# MSP-EXP430F5529LP.net
KiCad netlist of a schematic drawn in EAGLE
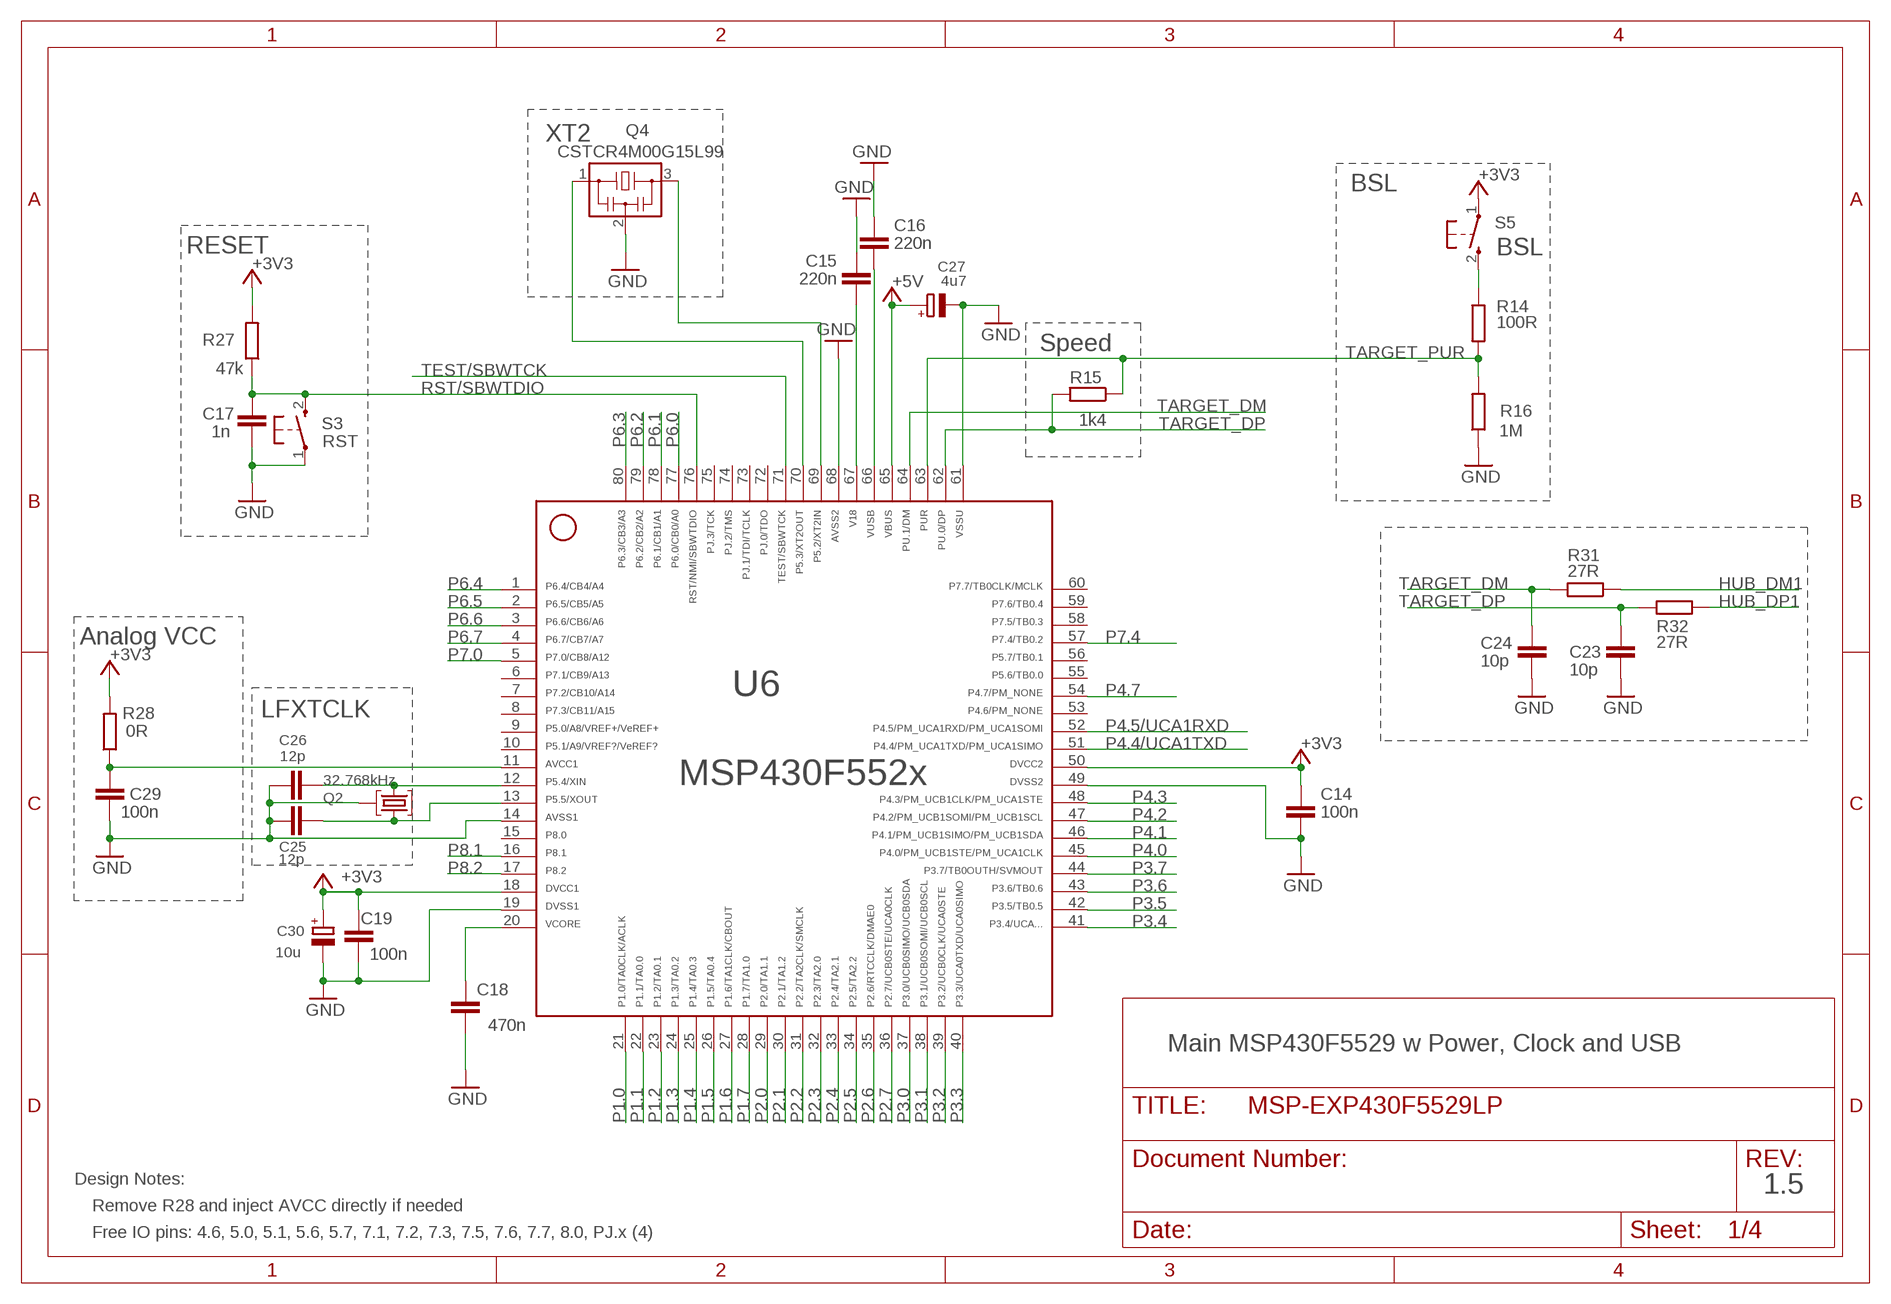
[diagram p0: schematic, sheet 1]
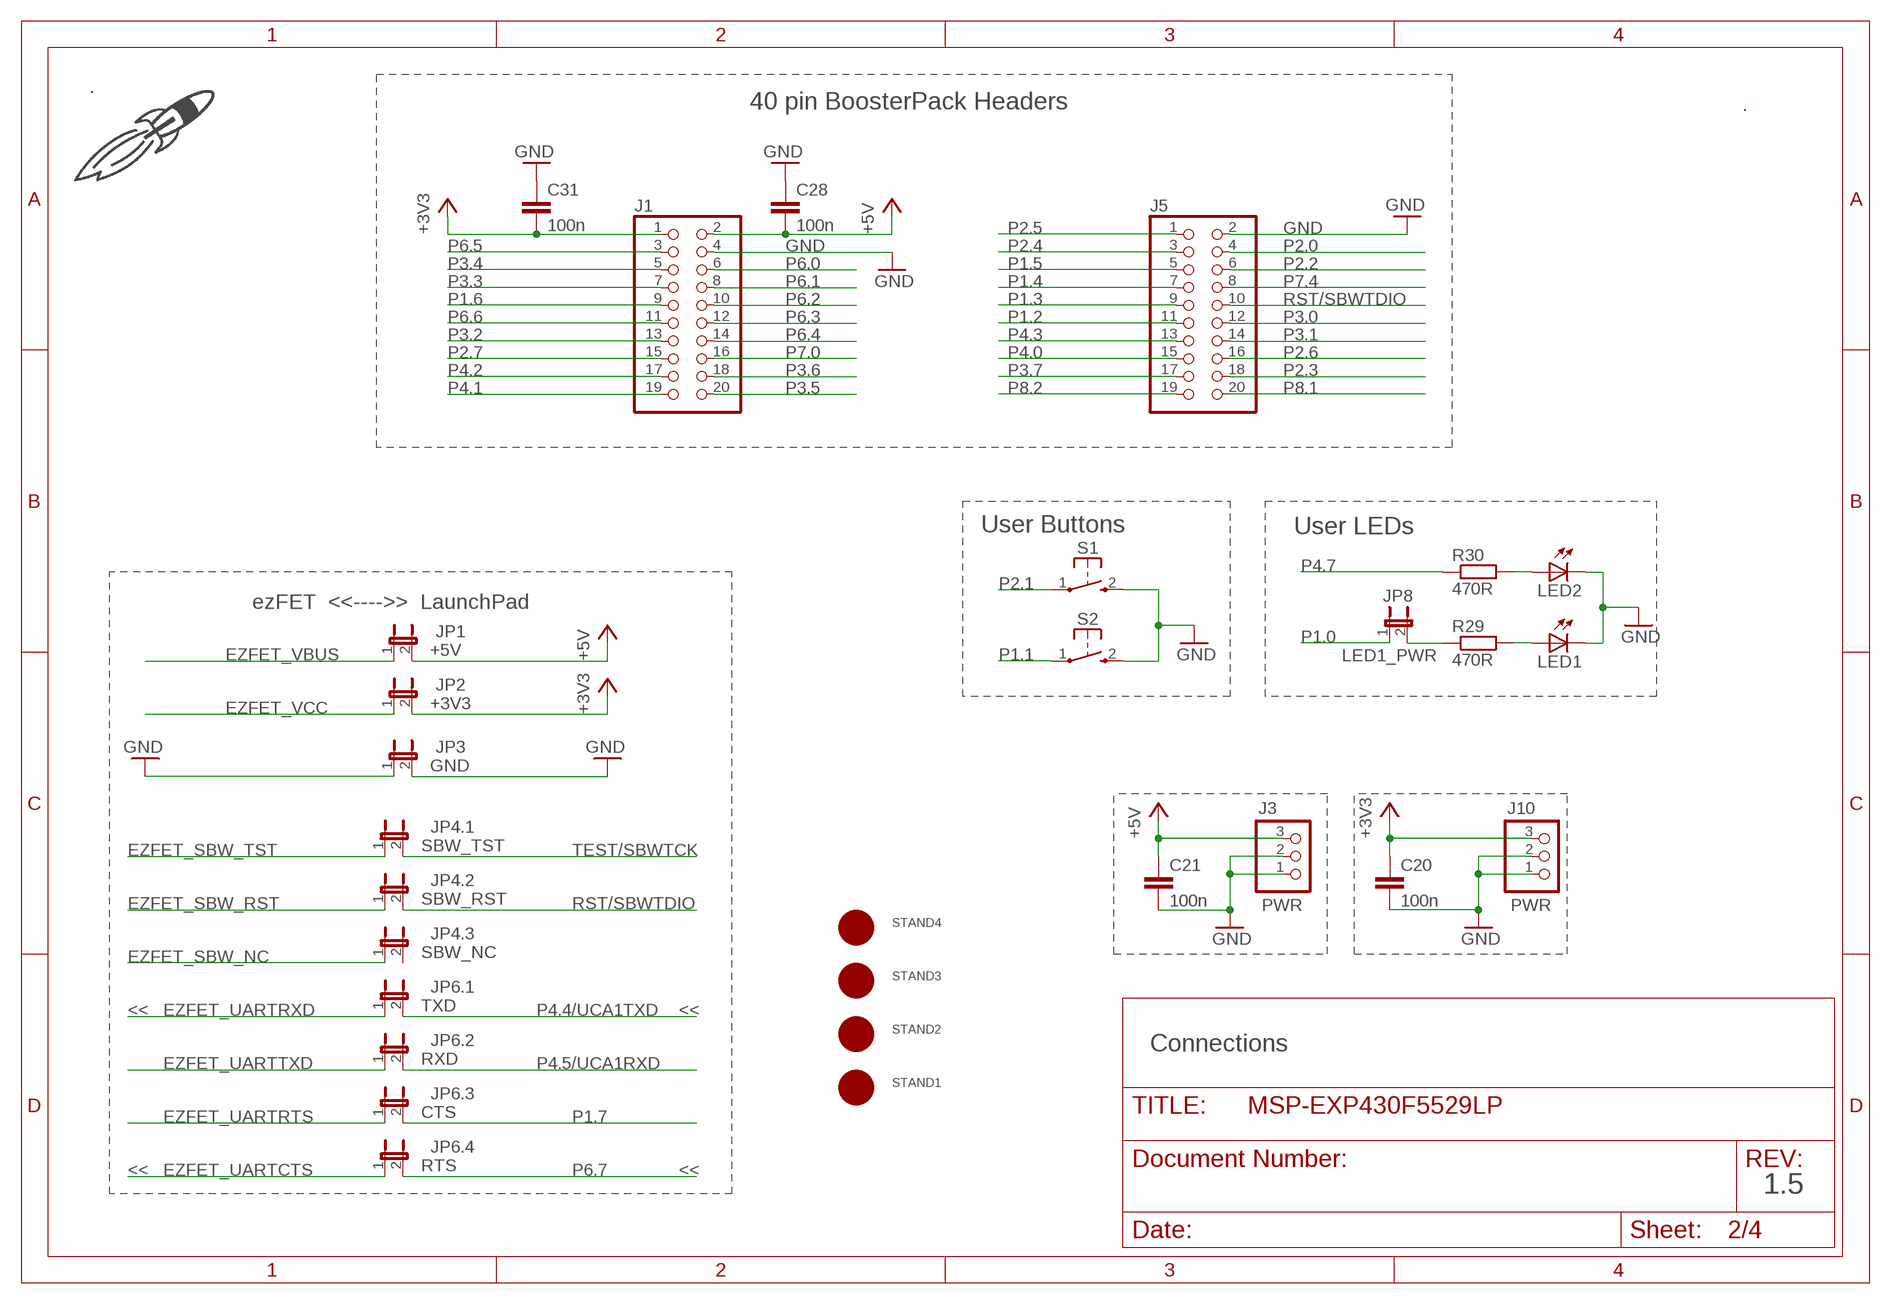
[diagram p1: schematic, sheet 2]
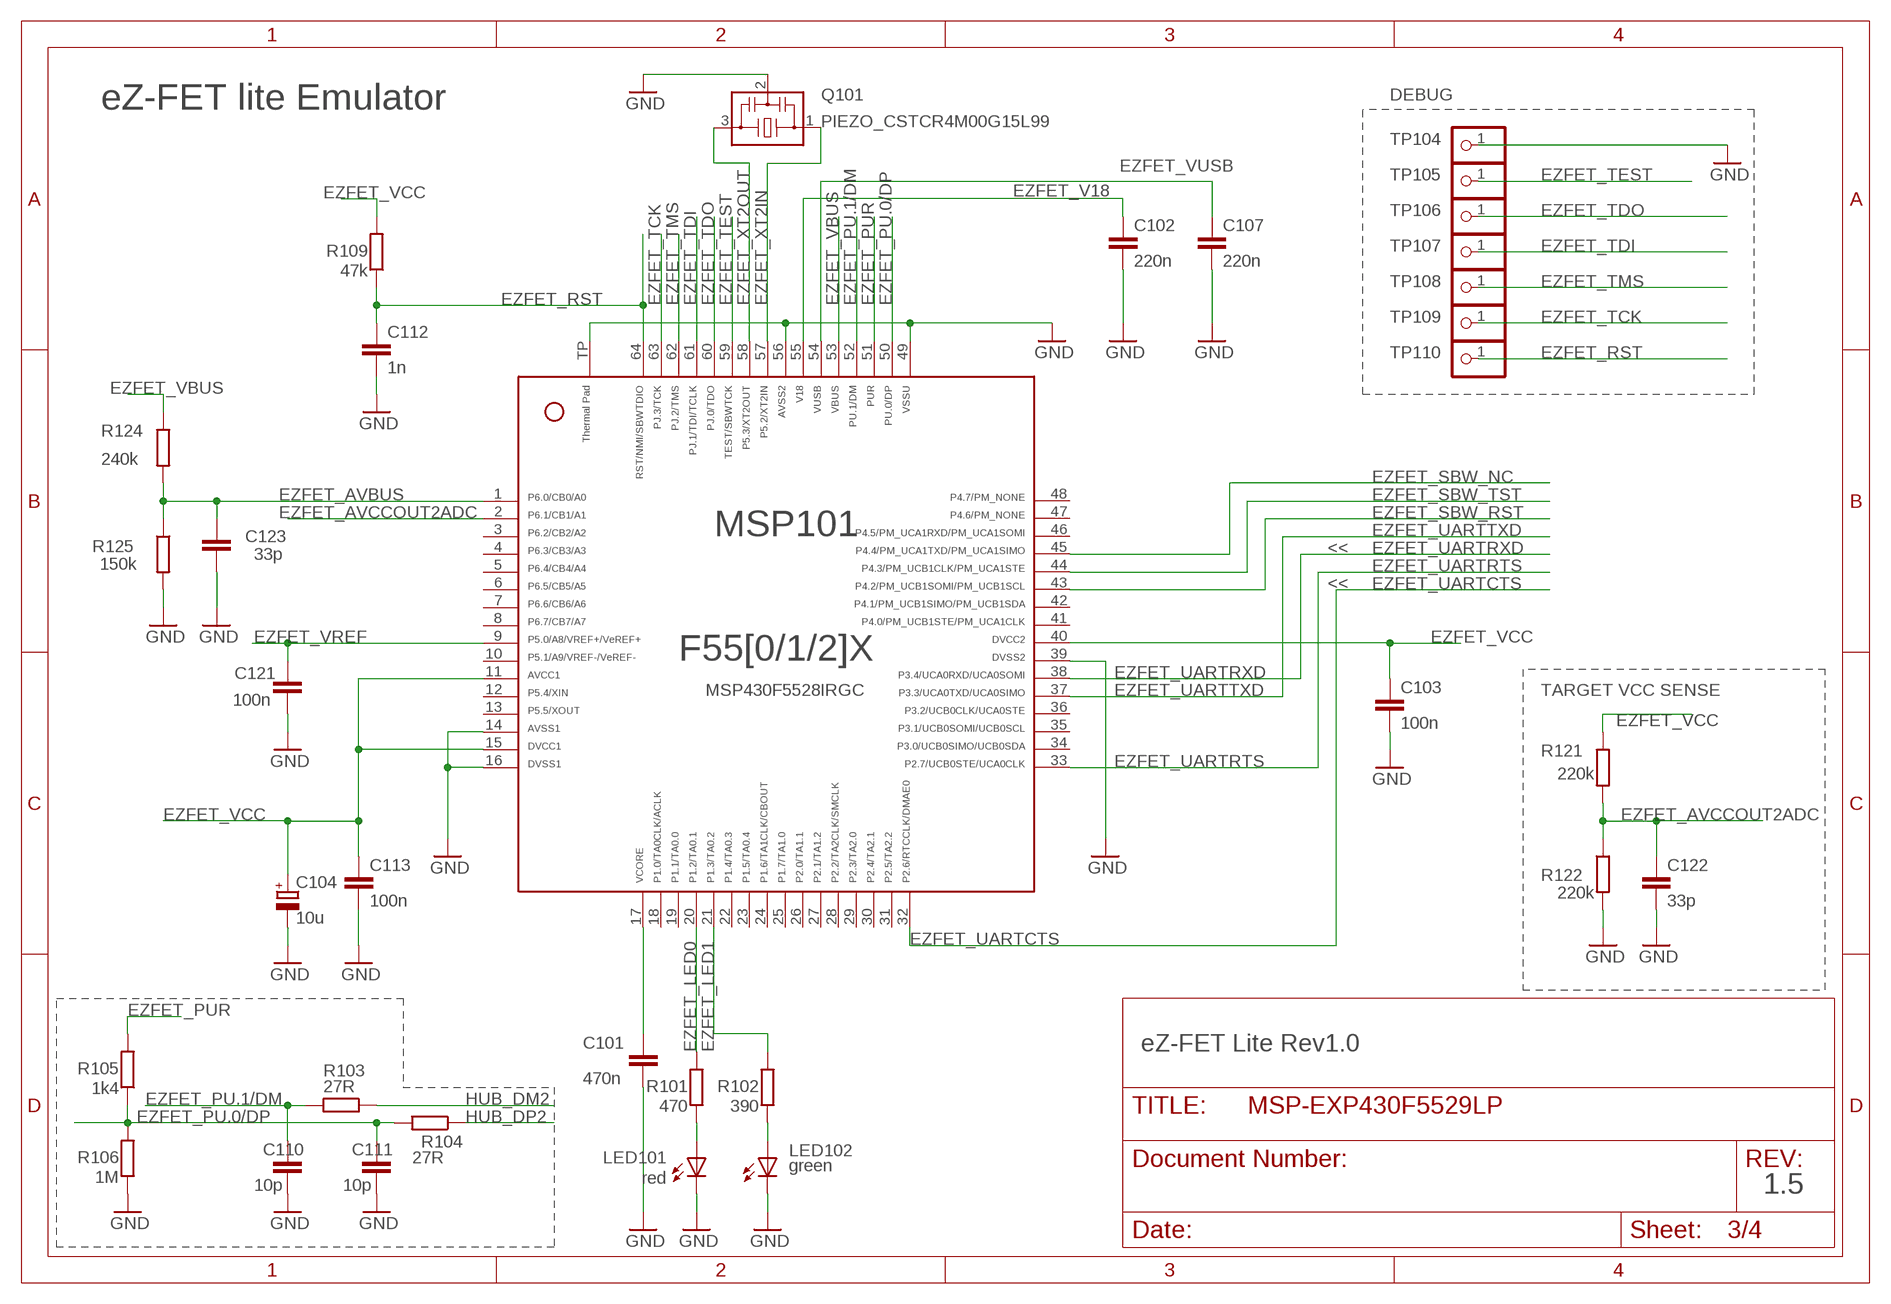
[diagram p2: schematic, sheet 3]
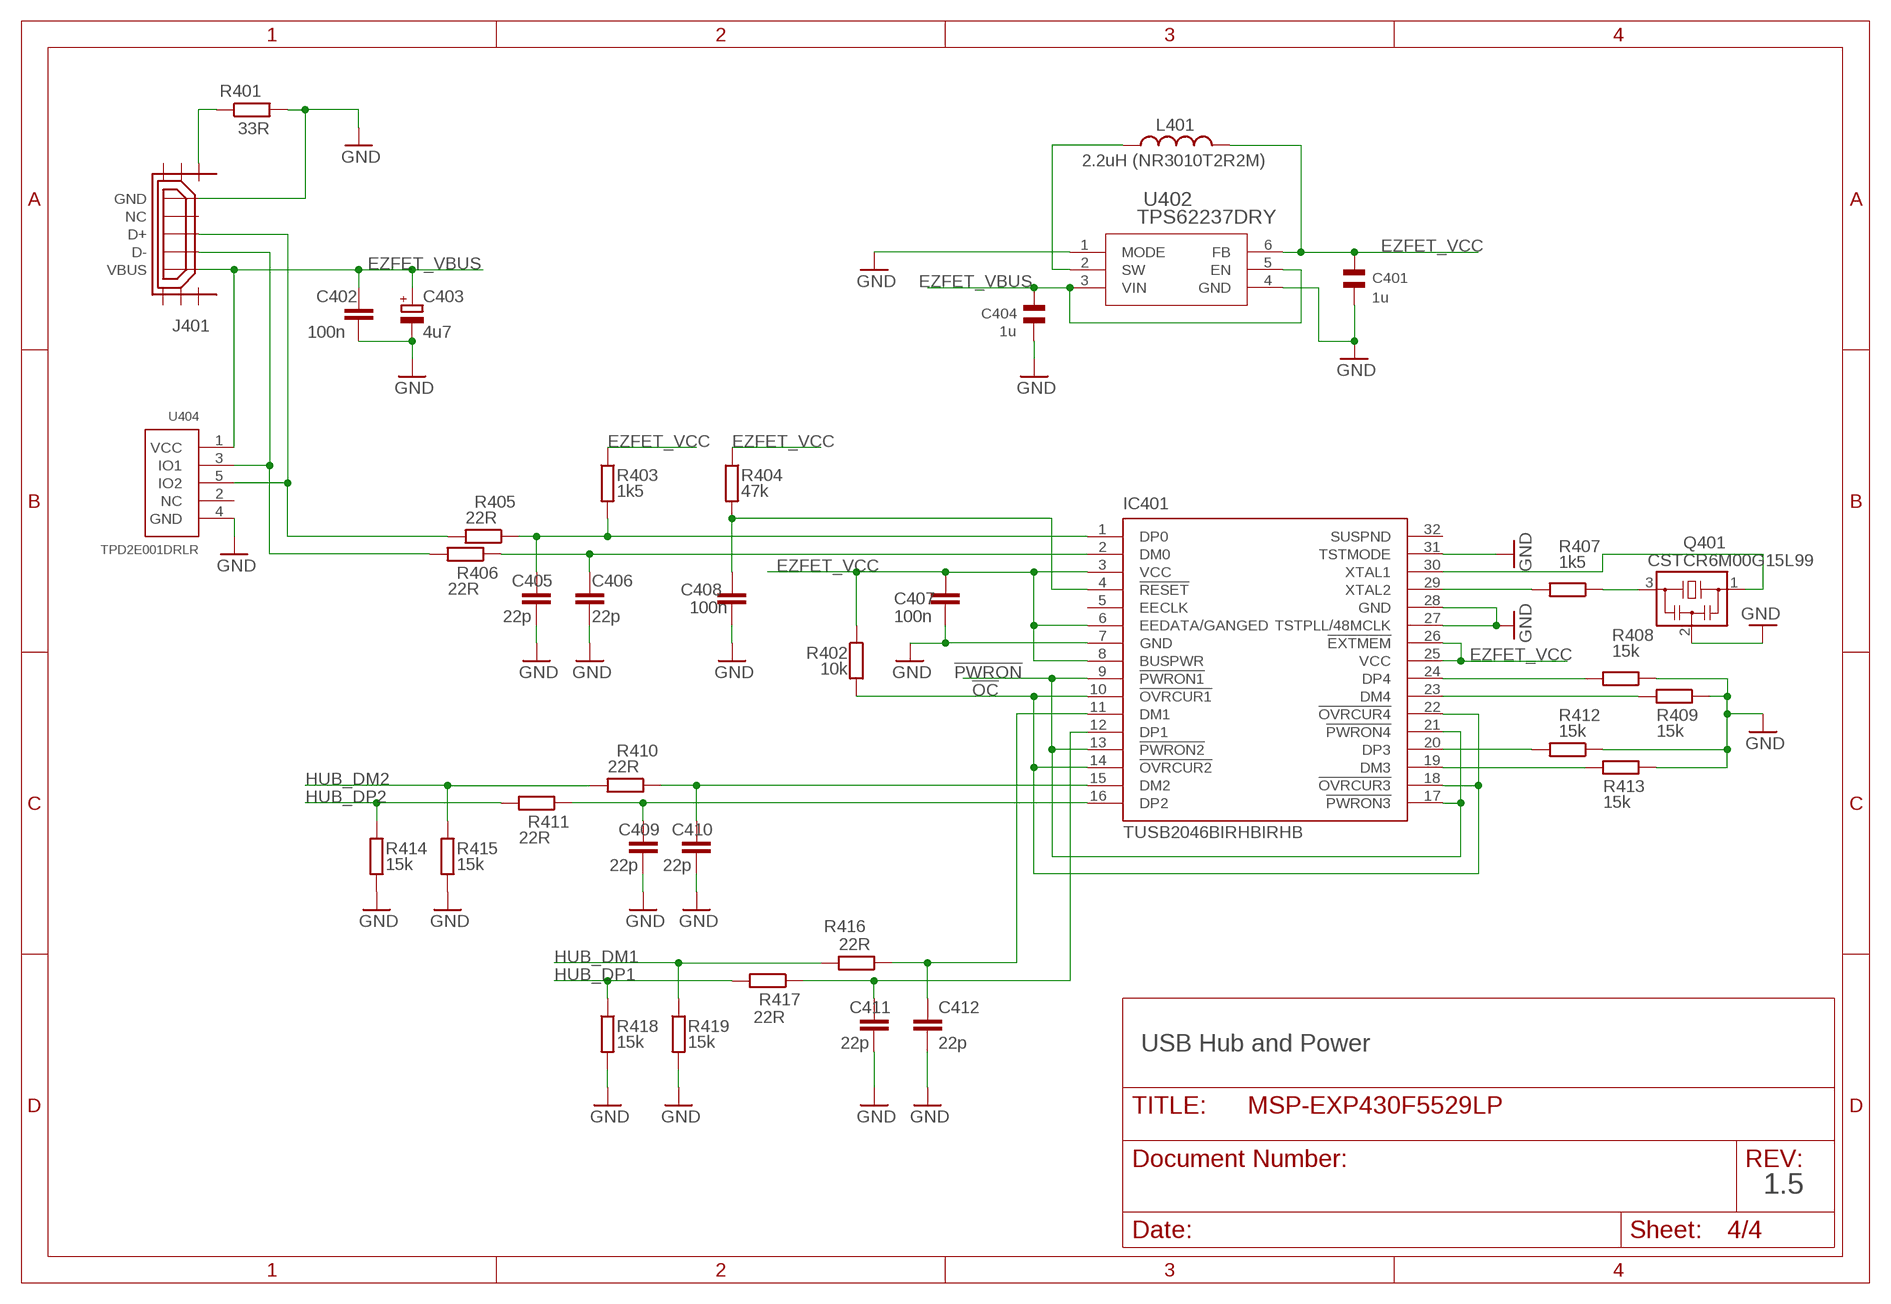
[diagram p3: schematic, sheet 4]

(export (version "E")
  (design (tool "Eeschema 10.0.6"))
  (components
    (comp (ref "C101")
      (value "470n")
      (footprint "eagle-import:C0402")
      (libsource (lib "eagle-import") (part "C-EUC0402"))
    )
    (comp (ref "C102")
      (value "220n")
      (footprint "eagle-import:C0402")
      (libsource (lib "eagle-import") (part "C-EUC0402"))
    )
    (comp (ref "C103")
      (value "100n")
      (footprint "eagle-import:C0402")
      (libsource (lib "eagle-import") (part "C-EUC0402"))
    )
    (comp (ref "C104")
      (value "10u")
      (footprint "eagle-import:A_3216-18R")
      (libsource (lib "eagle-import") (part "CPOL-EUA/3216-18R"))
    )
    (comp (ref "C107")
      (value "220n")
      (footprint "eagle-import:C0402")
      (libsource (lib "eagle-import") (part "C-EUC0402"))
    )
    (comp (ref "C110")
      (value "10p")
      (footprint "eagle-import:C0402")
      (libsource (lib "eagle-import") (part "C-EUC0402"))
    )
    (comp (ref "C111")
      (value "10p")
      (footprint "eagle-import:C0402")
      (libsource (lib "eagle-import") (part "C-EUC0402"))
    )
    (comp (ref "C112")
      (value "1n")
      (footprint "eagle-import:C0402")
      (libsource (lib "eagle-import") (part "C-EUC0402"))
    )
    (comp (ref "C113")
      (value "100n")
      (footprint "eagle-import:C0402")
      (libsource (lib "eagle-import") (part "C-EUC0402"))
    )
    (comp (ref "C121")
      (value "100n")
      (footprint "eagle-import:C0402")
      (libsource (lib "eagle-import") (part "C-EUC0402"))
    )
    (comp (ref "C122")
      (value "33p")
      (footprint "eagle-import:C0402")
      (libsource (lib "eagle-import") (part "C-EUC0402"))
    )
    (comp (ref "C123")
      (value "33p")
      (footprint "eagle-import:C0402")
      (libsource (lib "eagle-import") (part "C-EUC0402"))
    )
    (comp (ref "LED101")
      (value "red")
      (footprint "eagle-import:CHIP-LED0603")
      (libsource (lib "eagle-import") (part "LEDCHIP-LED0603"))
    )
    (comp (ref "LED102")
      (value "green")
      (footprint "eagle-import:CHIP-LED0603")
      (libsource (lib "eagle-import") (part "LEDCHIP-LED0603"))
    )
    (comp (ref "MSP101")
      (value "MSP430F5528IRGC")
      (footprint "eagle-import:RGC64")
      (libsource (lib "eagle-import") (part "F55[0/1/2]X---RGC64"))
    )
    (comp (ref "Q101")
      (value "PIEZO_CSTCR4M00G15L99")
      (footprint "eagle-import:MURATA-FILTER_CSTCR")
      (fields (field (name "MPN") "CSTCR6M00G53-R0"))
      (libsource (lib "eagle-import") (part "MURATA-FILTER_CSTCR6M00G53Z"))
    )
    (comp (ref "R101")
      (value "470")
      (footprint "eagle-import:R0402")
      (libsource (lib "eagle-import") (part "R-EU_R0402"))
    )
    (comp (ref "R102")
      (value "390")
      (footprint "eagle-import:R0402")
      (libsource (lib "eagle-import") (part "R-EU_R0402"))
    )
    (comp (ref "R103")
      (value "27R")
      (footprint "eagle-import:R0402")
      (libsource (lib "eagle-import") (part "R-EU_R0402"))
    )
    (comp (ref "R104")
      (value "27R")
      (footprint "eagle-import:R0402")
      (libsource (lib "eagle-import") (part "R-EU_R0402"))
    )
    (comp (ref "R105")
      (value "1k4")
      (footprint "eagle-import:R0402")
      (libsource (lib "eagle-import") (part "R-EU_R0402"))
    )
    (comp (ref "R106")
      (value "1M")
      (footprint "eagle-import:R0402")
      (libsource (lib "eagle-import") (part "R-EU_R0402"))
    )
    (comp (ref "R109")
      (value "47k")
      (footprint "eagle-import:R0402")
      (libsource (lib "eagle-import") (part "R-EU_R0402"))
    )
    (comp (ref "R121")
      (value "220k")
      (footprint "eagle-import:R0402")
      (libsource (lib "eagle-import") (part "R-EU_R0402"))
    )
    (comp (ref "R122")
      (value "220k")
      (footprint "eagle-import:R0402")
      (libsource (lib "eagle-import") (part "R-EU_R0402"))
    )
    (comp (ref "R124")
      (value "240k")
      (footprint "eagle-import:R0402")
      (libsource (lib "eagle-import") (part "R-EU_R0402"))
    )
    (comp (ref "R125")
      (value "150k")
      (footprint "eagle-import:R0402")
      (libsource (lib "eagle-import") (part "R-EU_R0402"))
    )
    (comp (ref "TP104")
      (value "TEST_PIN2")
      (footprint "eagle-import:1X01")
      (libsource (lib "eagle-import") (part "PINHD-1X1"))
    )
    (comp (ref "TP105")
      (value "TEST_PIN2")
      (footprint "eagle-import:1X01")
      (libsource (lib "eagle-import") (part "PINHD-1X1"))
    )
    (comp (ref "TP106")
      (value "TEST_PIN2")
      (footprint "eagle-import:1X01")
      (libsource (lib "eagle-import") (part "PINHD-1X1"))
    )
    (comp (ref "TP107")
      (value "TEST_PIN2")
      (footprint "eagle-import:1X01")
      (libsource (lib "eagle-import") (part "PINHD-1X1"))
    )
    (comp (ref "TP108")
      (value "TEST_PIN2")
      (footprint "eagle-import:1X01")
      (libsource (lib "eagle-import") (part "PINHD-1X1"))
    )
    (comp (ref "TP109")
      (value "TEST_PIN2")
      (footprint "eagle-import:1X01")
      (libsource (lib "eagle-import") (part "PINHD-1X1"))
    )
    (comp (ref "TP110")
      (value "TEST_PIN2")
      (footprint "eagle-import:1X01")
      (libsource (lib "eagle-import") (part "PINHD-1X1"))
    )
    (comp (ref "C401")
      (value "1u")
      (footprint "eagle-import:CSMD0805")
      (libsource (lib "eagle-import") (part "CSMD0805"))
    )
    (comp (ref "C402")
      (value "100n")
      (footprint "eagle-import:C0402")
      (libsource (lib "eagle-import") (part "C-EUC0402"))
    )
    (comp (ref "C403")
      (value "4u7")
      (footprint "eagle-import:A_3216-18R")
      (libsource (lib "eagle-import") (part "CPOL-EUA/3216-18R"))
    )
    (comp (ref "C404")
      (value "1u")
      (footprint "eagle-import:CSMD0805")
      (libsource (lib "eagle-import") (part "CSMD0805"))
    )
    (comp (ref "C405")
      (value "22p")
      (footprint "eagle-import:C0402")
      (libsource (lib "eagle-import") (part "C-EUC0402"))
    )
    (comp (ref "C406")
      (value "22p")
      (footprint "eagle-import:C0402")
      (libsource (lib "eagle-import") (part "C-EUC0402"))
    )
    (comp (ref "C407")
      (value "100n")
      (footprint "eagle-import:C0402")
      (libsource (lib "eagle-import") (part "C-EUC0402"))
    )
    (comp (ref "C408")
      (value "100n")
      (footprint "eagle-import:C0402")
      (libsource (lib "eagle-import") (part "C-EUC0402"))
    )
    (comp (ref "C409")
      (value "22p")
      (footprint "eagle-import:C0402")
      (libsource (lib "eagle-import") (part "C-EUC0402"))
    )
    (comp (ref "C410")
      (value "22p")
      (footprint "eagle-import:C0402")
      (libsource (lib "eagle-import") (part "C-EUC0402"))
    )
    (comp (ref "C411")
      (value "22p")
      (footprint "eagle-import:C0402")
      (libsource (lib "eagle-import") (part "C-EUC0402"))
    )
    (comp (ref "C412")
      (value "22p")
      (footprint "eagle-import:C0402")
      (libsource (lib "eagle-import") (part "C-EUC0402"))
    )
    (comp (ref "IC401")
      (value "TUSB2046BIRHBIRHB")
      (footprint "eagle-import:RHB_S-PQFP-N32")
      (fields (field (name "MPN") "TUSB2046BIRHBT"))
      (libsource (lib "eagle-import") (part "TUSB2046BIRHBIRHB"))
    )
    (comp (ref "J401")
      (value "USB_MICRO_FLIPPED")
      (footprint "eagle-import:HIROSE-ZX62R-B-5P")
      (libsource (lib "eagle-import") (part "USB_MICRO_FLIPPED"))
    )
    (comp (ref "L401")
      (value "2.2uH (NR3010T2R2M)")
      (footprint "eagle-import:L-NR3010")
      (libsource (lib "eagle-import") (part "L-NR3010"))
    )
    (comp (ref "Q401")
      (value "CSTCR6M00G15L99")
      (footprint "eagle-import:MURATA-FILTER_CSTCR")
      (fields (field (name "MPN") "CSTCR6M00G53-R0"))
      (libsource (lib "eagle-import") (part "MURATA-FILTER_CSTCR6M00G53Z"))
    )
    (comp (ref "R401")
      (value "33R")
      (footprint "eagle-import:R0402")
      (libsource (lib "eagle-import") (part "R-EU_R0402"))
    )
    (comp (ref "R402")
      (value "10k")
      (footprint "eagle-import:R0402")
      (libsource (lib "eagle-import") (part "R-EU_R0402"))
    )
    (comp (ref "R403")
      (value "1k5")
      (footprint "eagle-import:R0402")
      (libsource (lib "eagle-import") (part "R-EU_R0402"))
    )
    (comp (ref "R404")
      (value "47k")
      (footprint "eagle-import:R0402")
      (libsource (lib "eagle-import") (part "R-EU_R0402"))
    )
    (comp (ref "R405")
      (value "22R")
      (footprint "eagle-import:R0402")
      (libsource (lib "eagle-import") (part "R-EU_R0402"))
    )
    (comp (ref "R406")
      (value "22R")
      (footprint "eagle-import:R0402")
      (libsource (lib "eagle-import") (part "R-EU_R0402"))
    )
    (comp (ref "R407")
      (value "1k5")
      (footprint "eagle-import:R0402")
      (libsource (lib "eagle-import") (part "R-EU_R0402"))
    )
    (comp (ref "R408")
      (value "15k")
      (footprint "eagle-import:R0402")
      (libsource (lib "eagle-import") (part "R-EU_R0402"))
    )
    (comp (ref "R409")
      (value "15k")
      (footprint "eagle-import:R0402")
      (libsource (lib "eagle-import") (part "R-EU_R0402"))
    )
    (comp (ref "R410")
      (value "22R")
      (footprint "eagle-import:R0402")
      (libsource (lib "eagle-import") (part "R-EU_R0402"))
    )
    (comp (ref "R411")
      (value "22R")
      (footprint "eagle-import:R0402")
      (libsource (lib "eagle-import") (part "R-EU_R0402"))
    )
    (comp (ref "R412")
      (value "15k")
      (footprint "eagle-import:R0402")
      (libsource (lib "eagle-import") (part "R-EU_R0402"))
    )
    (comp (ref "R413")
      (value "15k")
      (footprint "eagle-import:R0402")
      (libsource (lib "eagle-import") (part "R-EU_R0402"))
    )
    (comp (ref "R414")
      (value "15k")
      (footprint "eagle-import:R0402")
      (libsource (lib "eagle-import") (part "R-EU_R0402"))
    )
    (comp (ref "R415")
      (value "15k")
      (footprint "eagle-import:R0402")
      (libsource (lib "eagle-import") (part "R-EU_R0402"))
    )
    (comp (ref "R416")
      (value "22R")
      (footprint "eagle-import:R0402")
      (libsource (lib "eagle-import") (part "R-EU_R0402"))
    )
    (comp (ref "R417")
      (value "22R")
      (footprint "eagle-import:R0402")
      (libsource (lib "eagle-import") (part "R-EU_R0402"))
    )
    (comp (ref "R418")
      (value "15k")
      (footprint "eagle-import:R0402")
      (libsource (lib "eagle-import") (part "R-EU_R0402"))
    )
    (comp (ref "R419")
      (value "15k")
      (footprint "eagle-import:R0402")
      (libsource (lib "eagle-import") (part "R-EU_R0402"))
    )
    (comp (ref "U402")
      (value "TPS62237DRY")
      (footprint "eagle-import:DRY6")
      (fields
        (field (name "GENERIC_PART_NUMBER") "TPS62231")
        (field (name "MANUFACTURER") "Texas Instruments")
        (field (name "MANUFACTURER_PART_NUMBER") "tps62231_dry_6")
      )
      (libsource (lib "eagle-import") (part "TPS6223X_DRY_6"))
    )
    (comp (ref "U404")
      (value "TPD2E001DRLR")
      (footprint "eagle-import:TPD2E001-DRL")
      (libsource (lib "eagle-import") (part "TPD2E001"))
    )
    (comp (ref "C14")
      (value "100n")
      (footprint "eagle-import:C0402")
      (libsource (lib "eagle-import") (part "C-EUC0402"))
    )
    (comp (ref "C15")
      (value "220n")
      (footprint "eagle-import:C0402")
      (libsource (lib "eagle-import") (part "C-EUC0402"))
    )
    (comp (ref "C16")
      (value "220n")
      (footprint "eagle-import:C0402")
      (libsource (lib "eagle-import") (part "C-EUC0402"))
    )
    (comp (ref "C17")
      (value "1n")
      (footprint "eagle-import:C0402")
      (libsource (lib "eagle-import") (part "C-EUC0402"))
    )
    (comp (ref "C18")
      (value "470n")
      (footprint "eagle-import:C0402")
      (libsource (lib "eagle-import") (part "C-EUC0402"))
    )
    (comp (ref "C19")
      (value "100n")
      (footprint "eagle-import:C0402")
      (libsource (lib "eagle-import") (part "C-EUC0402"))
    )
    (comp (ref "C23")
      (value "10p")
      (footprint "eagle-import:C0402")
      (libsource (lib "eagle-import") (part "C-EUC0402"))
    )
    (comp (ref "C24")
      (value "10p")
      (footprint "eagle-import:C0402")
      (libsource (lib "eagle-import") (part "C-EUC0402"))
    )
    (comp (ref "C25")
      (value "12p")
      (footprint "eagle-import:C0402")
      (libsource (lib "eagle-import") (part "C-EUC0402"))
    )
    (comp (ref "C26")
      (value "12p")
      (footprint "eagle-import:C0402")
      (libsource (lib "eagle-import") (part "C-EUC0402"))
    )
    (comp (ref "C27")
      (value "4u7")
      (footprint "eagle-import:A_3216-18R")
      (libsource (lib "eagle-import") (part "CPOL-EUA/3216-18R"))
    )
    (comp (ref "C29")
      (value "100n")
      (footprint "eagle-import:C0402")
      (libsource (lib "eagle-import") (part "C-EUC0402"))
    )
    (comp (ref "C30")
      (value "10u")
      (footprint "eagle-import:A_3216-18R")
      (libsource (lib "eagle-import") (part "CPOL-EUA/3216-18R"))
    )
    (comp (ref "Q2")
      (value "32.768kHz")
      (footprint "eagle-import:MS3V-T1R")
      (libsource (lib "eagle-import") (part "MS3V-T1R"))
    )
    (comp (ref "Q4")
      (value "CSTCR4M00G15L99")
      (footprint "eagle-import:MURATA-FILTER_CSTCR")
      (fields (field (name "MPN") "CSTCR6M00G53-R0"))
      (libsource (lib "eagle-import") (part "MURATA-FILTER_CSTCR6M00G53Z"))
    )
    (comp (ref "R14")
      (value "100R")
      (footprint "eagle-import:R0402")
      (libsource (lib "eagle-import") (part "R-EU_R0402"))
    )
    (comp (ref "R15")
      (value "1k4")
      (footprint "eagle-import:R0402")
      (libsource (lib "eagle-import") (part "R-EU_R0402"))
    )
    (comp (ref "R16")
      (value "1M")
      (footprint "eagle-import:R0402")
      (libsource (lib "eagle-import") (part "R-EU_R0402"))
    )
    (comp (ref "R27")
      (value "47k")
      (footprint "eagle-import:R0402")
      (libsource (lib "eagle-import") (part "R-EU_R0402"))
    )
    (comp (ref "R28")
      (value "0R")
      (footprint "eagle-import:R0402")
      (libsource (lib "eagle-import") (part "R-EU_R0402"))
    )
    (comp (ref "R31")
      (value "27R")
      (footprint "eagle-import:R0402")
      (libsource (lib "eagle-import") (part "R-EU_R0402"))
    )
    (comp (ref "R32")
      (value "27R")
      (footprint "eagle-import:R0402")
      (libsource (lib "eagle-import") (part "R-EU_R0402"))
    )
    (comp (ref "S3")
      (value "RST")
      (footprint "eagle-import:PBTH")
      (libsource (lib "eagle-import") (part "PB"))
    )
    (comp (ref "S5")
      (value "BSL")
      (footprint "eagle-import:PBTH")
      (libsource (lib "eagle-import") (part "PB"))
    )
    (comp (ref "U6")
      (value "MSP430F5529IPNR")
      (footprint "eagle-import:PN80")
      (libsource (lib "eagle-import") (part "F552X---PN80"))
    )
    (comp (ref "C20")
      (value "100n")
      (footprint "eagle-import:C0402")
      (libsource (lib "eagle-import") (part "C-EUC0402"))
    )
    (comp (ref "C21")
      (value "100n")
      (footprint "eagle-import:C0402")
      (libsource (lib "eagle-import") (part "C-EUC0402"))
    )
    (comp (ref "C28")
      (value "100n")
      (footprint "eagle-import:C0402")
      (libsource (lib "eagle-import") (part "C-EUC0402"))
    )
    (comp (ref "C31")
      (value "100n")
      (footprint "eagle-import:C0402")
      (libsource (lib "eagle-import") (part "C-EUC0402"))
    )
    (comp (ref "DRAW1")
      (value "LOGO-ROCKET-20X13MM-SCH-S")
      (footprint "eagle-import:LOGO-ROCKET-10X7MM-BRD")
      (libsource (lib "eagle-import") (part "LOGO-ROCKET-20X13MM-SCH-S"))
    )
    (comp (ref "J1")
      (value "PINHD-2X10")
      (footprint "eagle-import:2X10")
      (libsource (lib "eagle-import") (part "PINHD-2X10"))
    )
    (comp (ref "J3")
      (value "PWR")
      (footprint "eagle-import:1X03")
      (libsource (lib "eagle-import") (part "PINHD-1X3"))
    )
    (comp (ref "J5")
      (value "PINHD-2X10")
      (footprint "eagle-import:2X10")
      (libsource (lib "eagle-import") (part "PINHD-2X10"))
    )
    (comp (ref "J10")
      (value "PWR")
      (footprint "eagle-import:1X03")
      (libsource (lib "eagle-import") (part "PINHD-1X3"))
    )
    (comp (ref "JP1")
      (value "+5V")
      (footprint "eagle-import:JP1M")
      (libsource (lib "eagle-import") (part "JP1M"))
    )
    (comp (ref "JP2")
      (value "+3V3")
      (footprint "eagle-import:JP1M")
      (libsource (lib "eagle-import") (part "JP1M"))
    )
    (comp (ref "JP3")
      (value "GND")
      (footprint "eagle-import:JP1M")
      (libsource (lib "eagle-import") (part "JP1M"))
    )
    (comp (ref "JP4.1")
      (value "SBW_TST")
      (footprint "eagle-import:JP1M")
      (libsource (lib "eagle-import") (part "JP1M"))
    )
    (comp (ref "JP4.2")
      (value "SBW_RST")
      (footprint "eagle-import:JP1M")
      (libsource (lib "eagle-import") (part "JP1M"))
    )
    (comp (ref "JP4.3")
      (value "SBW_NC")
      (footprint "eagle-import:JP1M")
      (libsource (lib "eagle-import") (part "JP1M"))
    )
    (comp (ref "JP6.1")
      (value "TXD")
      (footprint "eagle-import:JP1M")
      (libsource (lib "eagle-import") (part "JP1M"))
    )
    (comp (ref "JP6.2")
      (value "RXD")
      (footprint "eagle-import:JP1M")
      (libsource (lib "eagle-import") (part "JP1M"))
    )
    (comp (ref "JP6.3")
      (value "CTS")
      (footprint "eagle-import:JP1M")
      (libsource (lib "eagle-import") (part "JP1M"))
    )
    (comp (ref "JP6.4")
      (value "RTS")
      (footprint "eagle-import:JP1M")
      (libsource (lib "eagle-import") (part "JP1M"))
    )
    (comp (ref "JP8")
      (value "LED1_PWR")
      (footprint "eagle-import:JP1")
      (libsource (lib "eagle-import") (part "JP1E"))
    )
    (comp (ref "LED1")
      (value "LEDCHIPLED_0603")
      (footprint "eagle-import:CHIPLED_0603")
      (libsource (lib "eagle-import") (part "LEDCHIPLED_0603"))
    )
    (comp (ref "LED2")
      (value "LEDCHIPLED_0603")
      (footprint "eagle-import:CHIPLED_0603")
      (libsource (lib "eagle-import") (part "LEDCHIPLED_0603"))
    )
    (comp (ref "R29")
      (value "470R")
      (footprint "eagle-import:R0402")
      (libsource (lib "eagle-import") (part "R-EU_R0402"))
    )
    (comp (ref "R30")
      (value "470R")
      (footprint "eagle-import:R0402")
      (libsource (lib "eagle-import") (part "R-EU_R0402"))
    )
    (comp (ref "S1")
      (value "PB")
      (footprint "eagle-import:PBTH")
      (libsource (lib "eagle-import") (part "PB"))
    )
    (comp (ref "S2")
      (value "PB")
      (footprint "eagle-import:PBTH")
      (libsource (lib "eagle-import") (part "PB"))
    )
    (comp (ref "STAND1")
      (value "MOUNT")
      (footprint "eagle-import:MOUNTHOLE_110MIL")
      (libsource (lib "eagle-import") (part "MOUNT"))
    )
    (comp (ref "STAND2")
      (value "MOUNT")
      (footprint "eagle-import:MOUNTHOLE_110MIL")
      (libsource (lib "eagle-import") (part "MOUNT"))
    )
    (comp (ref "STAND3")
      (value "MOUNT")
      (footprint "eagle-import:MOUNTHOLE_110MIL")
      (libsource (lib "eagle-import") (part "MOUNT"))
    )
    (comp (ref "STAND4")
      (value "MOUNT")
      (footprint "eagle-import:MOUNTHOLE_110MIL")
      (libsource (lib "eagle-import") (part "MOUNT"))
    )
    (comp (ref "U$3")
      (value "5529_REAR_SILK_REV1_5_FINAL")
      (footprint "eagle-import:5529_REAR_SILK_REV1_5_FINAL")
      (libsource (lib "eagle-import") (part "5529_REAR_SILK_REV1_5_FINAL"))
    )
    (comp (ref "U$4")
      (value "MS_TM")
      (footprint "eagle-import:MS_TM")
      (libsource (lib "eagle-import") (part "MS_TM"))
    )
  )
  (nets
    (net (code "1") (name "+3V3") (class "Default")
      (node (ref "C14") (pin "1") (pinfunction "1_1") (pintype "passive"))
      (node (ref "C19") (pin "2") (pinfunction "2_2") (pintype "passive"))
      (node (ref "C20") (pin "1") (pinfunction "1_1") (pintype "passive"))
      (node (ref "C30") (pin "+") (pinfunction "+_+") (pintype "passive"))
      (node (ref "C31") (pin "2") (pinfunction "2_2") (pintype "passive"))
      (node (ref "J1") (pin "1") (pinfunction "1_1") (pintype "passive"))
      (node (ref "J10") (pin "3") (pinfunction "3_3") (pintype "passive"))
      (node (ref "JP2") (pin "2") (pinfunction "2_2") (pintype "passive"))
      (node (ref "R27") (pin "2") (pinfunction "2_2") (pintype "passive"))
      (node (ref "R28") (pin "2") (pinfunction "2_2") (pintype "passive"))
      (node (ref "S5") (pin "1") (pinfunction "P_1") (pintype "passive"))
      (node (ref "U6") (pin "18") (pinfunction "18_18") (pintype "power_in"))
      (node (ref "U6") (pin "50") (pinfunction "50_50") (pintype "power_in"))
    )
    (net (code "2") (name "+5V") (class "Default")
      (node (ref "C21") (pin "1") (pinfunction "1_1") (pintype "passive"))
      (node (ref "C27") (pin "+") (pinfunction "+_+") (pintype "passive"))
      (node (ref "C28") (pin "2") (pinfunction "2_2") (pintype "passive"))
      (node (ref "J1") (pin "2") (pinfunction "2_2") (pintype "passive"))
      (node (ref "J3") (pin "3") (pinfunction "3_3") (pintype "passive"))
      (node (ref "JP1") (pin "2") (pinfunction "2_2") (pintype "passive"))
      (node (ref "U6") (pin "65") (pinfunction "65_65") (pintype "power_in"))
    )
    (net (code "3") (name "EZFET_AVBUS") (class "Default")
      (node (ref "C123") (pin "2") (pinfunction "2_2") (pintype "passive"))
      (node (ref "MSP101") (pin "1") (pinfunction "1_1") (pintype "bidirectional"))
      (node (ref "R124") (pin "2") (pinfunction "2_2") (pintype "passive"))
      (node (ref "R125") (pin "1") (pinfunction "1_1") (pintype "passive"))
    )
    (net (code "4") (name "EZFET_AVCCOUT2ADC") (class "Default")
      (node (ref "C122") (pin "2") (pinfunction "2_2") (pintype "passive"))
      (node (ref "MSP101") (pin "2") (pinfunction "2_2") (pintype "bidirectional"))
      (node (ref "R121") (pin "2") (pinfunction "2_2") (pintype "passive"))
      (node (ref "R122") (pin "1") (pinfunction "1_1") (pintype "passive"))
    )
    (net (code "5") (name "EZFET_LED0") (class "Default")
      (node (ref "MSP101") (pin "20") (pinfunction "20_20") (pintype "bidirectional"))
      (node (ref "R101") (pin "2") (pinfunction "2_2") (pintype "passive"))
    )
    (net (code "6") (name "EZFET_LED1") (class "Default")
      (node (ref "MSP101") (pin "21") (pinfunction "21_21") (pintype "bidirectional"))
      (node (ref "R102") (pin "2") (pinfunction "2_2") (pintype "passive"))
    )
    (net (code "7") (name "EZFET_PU.0{slash}DP") (class "Default")
      (node (ref "C111") (pin "1") (pinfunction "1_1") (pintype "passive"))
      (node (ref "MSP101") (pin "50") (pinfunction "50_50") (pintype "bidirectional"))
      (node (ref "R104") (pin "2") (pinfunction "2_2") (pintype "passive"))
      (node (ref "R105") (pin "1") (pinfunction "1_1") (pintype "passive"))
      (node (ref "R106") (pin "2") (pinfunction "2_2") (pintype "passive"))
    )
    (net (code "8") (name "EZFET_PU.1{slash}DM") (class "Default")
      (node (ref "C110") (pin "1") (pinfunction "1_1") (pintype "passive"))
      (node (ref "MSP101") (pin "52") (pinfunction "52_52") (pintype "bidirectional"))
      (node (ref "R103") (pin "2") (pinfunction "2_2") (pintype "passive"))
    )
    (net (code "9") (name "EZFET_PUR") (class "Default")
      (node (ref "MSP101") (pin "51") (pinfunction "51_51") (pintype "bidirectional"))
      (node (ref "R105") (pin "2") (pinfunction "2_2") (pintype "passive"))
    )
    (net (code "10") (name "EZFET_RST") (class "Default")
      (node (ref "C112") (pin "1") (pinfunction "1_1") (pintype "passive"))
      (node (ref "MSP101") (pin "64") (pinfunction "64_64") (pintype "bidirectional"))
      (node (ref "R109") (pin "1") (pinfunction "1_1") (pintype "passive"))
      (node (ref "TP110") (pin "1") (pinfunction "1_1") (pintype "passive"))
    )
    (net (code "11") (name "EZFET_SBW_NC") (class "Default")
      (node (ref "JP4.3") (pin "1") (pinfunction "1_1") (pintype "passive"))
      (node (ref "MSP101") (pin "45") (pinfunction "45_45") (pintype "bidirectional"))
    )
    (net (code "12") (name "EZFET_SBW_RST") (class "Default")
      (node (ref "JP4.2") (pin "1") (pinfunction "1_1") (pintype "passive"))
      (node (ref "MSP101") (pin "43") (pinfunction "43_43") (pintype "bidirectional"))
    )
    (net (code "13") (name "EZFET_SBW_TST") (class "Default")
      (node (ref "JP4.1") (pin "1") (pinfunction "1_1") (pintype "passive"))
      (node (ref "MSP101") (pin "44") (pinfunction "44_44") (pintype "bidirectional"))
    )
    (net (code "14") (name "EZFET_TCK") (class "Default")
      (node (ref "MSP101") (pin "63") (pinfunction "63_63") (pintype "bidirectional"))
      (node (ref "TP109") (pin "1") (pinfunction "1_1") (pintype "passive"))
    )
    (net (code "15") (name "EZFET_TDI") (class "Default")
      (node (ref "MSP101") (pin "61") (pinfunction "61_61") (pintype "bidirectional"))
      (node (ref "TP107") (pin "1") (pinfunction "1_1") (pintype "passive"))
    )
    (net (code "16") (name "EZFET_TDO") (class "Default")
      (node (ref "MSP101") (pin "60") (pinfunction "60_60") (pintype "bidirectional"))
      (node (ref "TP106") (pin "1") (pinfunction "1_1") (pintype "passive"))
    )
    (net (code "17") (name "EZFET_TEST") (class "Default")
      (node (ref "MSP101") (pin "59") (pinfunction "59_59") (pintype "input"))
      (node (ref "TP105") (pin "1") (pinfunction "1_1") (pintype "passive"))
    )
    (net (code "18") (name "EZFET_TMS") (class "Default")
      (node (ref "MSP101") (pin "62") (pinfunction "62_62") (pintype "bidirectional"))
      (node (ref "TP108") (pin "1") (pinfunction "1_1") (pintype "passive"))
    )
    (net (code "19") (name "EZFET_UARTCTS") (class "Default")
      (node (ref "JP6.4") (pin "1") (pinfunction "1_1") (pintype "passive"))
      (node (ref "MSP101") (pin "32") (pinfunction "32_32") (pintype "bidirectional"))
    )
    (net (code "20") (name "EZFET_UARTRTS") (class "Default")
      (node (ref "JP6.3") (pin "1") (pinfunction "1_1") (pintype "passive"))
      (node (ref "MSP101") (pin "33") (pinfunction "33_33") (pintype "bidirectional"))
    )
    (net (code "21") (name "EZFET_UARTRXD") (class "Default")
      (node (ref "JP6.1") (pin "1") (pinfunction "1_1") (pintype "passive"))
      (node (ref "MSP101") (pin "38") (pinfunction "38_38") (pintype "bidirectional"))
    )
    (net (code "22") (name "EZFET_UARTTXD") (class "Default")
      (node (ref "JP6.2") (pin "1") (pinfunction "1_1") (pintype "passive"))
      (node (ref "MSP101") (pin "37") (pinfunction "37_37") (pintype "bidirectional"))
    )
    (net (code "23") (name "EZFET_V18") (class "Default")
      (node (ref "C102") (pin "1") (pinfunction "1_1") (pintype "passive"))
      (node (ref "MSP101") (pin "55") (pinfunction "55_55") (pintype "power_in"))
    )
    (net (code "24") (name "EZFET_VBUS") (class "Default")
      (node (ref "C402") (pin "1") (pinfunction "1_1") (pintype "passive"))
      (node (ref "C403") (pin "+") (pinfunction "+_+") (pintype "passive"))
      (node (ref "C404") (pin "2") (pinfunction "2_2") (pintype "passive"))
      (node (ref "J401") (pin "VBUS") (pinfunction "VBUS_VBUS") (pintype "input"))
      (node (ref "JP1") (pin "1") (pinfunction "1_1") (pintype "passive"))
      (node (ref "MSP101") (pin "53") (pinfunction "53_53") (pintype "power_in"))
      (node (ref "R124") (pin "1") (pinfunction "1_1") (pintype "passive"))
      (node (ref "U402") (pin "3") (pinfunction "VIN_3") (pintype "power_in"))
      (node (ref "U402") (pin "5") (pinfunction "EN_5") (pintype "input"))
      (node (ref "U404") (pin "1") (pinfunction "VCC_1") (pintype "power_in"))
    )
    (net (code "25") (name "EZFET_VCC") (class "Default")
      (node (ref "C103") (pin "1") (pinfunction "1_1") (pintype "passive"))
      (node (ref "C104") (pin "+") (pinfunction "+_+") (pintype "passive"))
      (node (ref "C113") (pin "1") (pinfunction "1_1") (pintype "passive"))
      (node (ref "C401") (pin "2") (pinfunction "2_2") (pintype "passive"))
      (node (ref "C407") (pin "1") (pinfunction "1_1") (pintype "passive"))
      (node (ref "IC401") (pin "25") (pinfunction "VCC_25") (pintype "power_in"))
      (node (ref "IC401") (pin "26") (pinfunction "~{EXTMEM}_26") (pintype "input"))
      (node (ref "IC401") (pin "3") (pinfunction "VCC_3") (pintype "power_in"))
      (node (ref "IC401") (pin "6") (pinfunction "EEDATA/GANGED_6") (pintype "bidirectional"))
      (node (ref "IC401") (pin "8") (pinfunction "BUSPWR_8") (pintype "input"))
      (node (ref "JP2") (pin "1") (pinfunction "1_1") (pintype "passive"))
      (node (ref "L401") (pin "P$2") (pinfunction "2_P$2") (pintype "passive"))
      (node (ref "MSP101") (pin "11") (pinfunction "11_11") (pintype "power_in"))
      (node (ref "MSP101") (pin "15") (pinfunction "15_15") (pintype "power_in"))
      (node (ref "MSP101") (pin "40") (pinfunction "40_40") (pintype "power_in"))
      (node (ref "R109") (pin "2") (pinfunction "2_2") (pintype "passive"))
      (node (ref "R121") (pin "1") (pinfunction "1_1") (pintype "passive"))
      (node (ref "R402") (pin "1") (pinfunction "1_1") (pintype "passive"))
      (node (ref "R403") (pin "1") (pinfunction "1_1") (pintype "passive"))
      (node (ref "R404") (pin "1") (pinfunction "1_1") (pintype "passive"))
      (node (ref "U402") (pin "6") (pinfunction "FB_6") (pintype "input"))
    )
    (net (code "26") (name "EZFET_VREF") (class "Default")
      (node (ref "C121") (pin "1") (pinfunction "1_1") (pintype "passive"))
      (node (ref "MSP101") (pin "9") (pinfunction "9_9") (pintype "output"))
    )
    (net (code "27") (name "EZFET_VUSB") (class "Default")
      (node (ref "C107") (pin "1") (pinfunction "1_1") (pintype "passive"))
      (node (ref "MSP101") (pin "54") (pinfunction "54_54") (pintype "power_in"))
    )
    (net (code "28") (name "EZFET_XT2IN") (class "Default")
      (node (ref "MSP101") (pin "57") (pinfunction "57_57") (pintype "bidirectional"))
      (node (ref "Q101") (pin "1") (pinfunction "1_1") (pintype "passive"))
    )
    (net (code "29") (name "EZFET_XT2OUT") (class "Default")
      (node (ref "MSP101") (pin "58") (pinfunction "58_58") (pintype "bidirectional"))
      (node (ref "Q101") (pin "3") (pinfunction "3_3") (pintype "passive"))
    )
    (net (code "30") (name "GND") (class "Default")
      (node (ref "C101") (pin "2") (pinfunction "2_2") (pintype "passive"))
      (node (ref "C102") (pin "2") (pinfunction "2_2") (pintype "passive"))
      (node (ref "C103") (pin "2") (pinfunction "2_2") (pintype "passive"))
      (node (ref "C104") (pin "-") (pinfunction "-_-") (pintype "passive"))
      (node (ref "C107") (pin "2") (pinfunction "2_2") (pintype "passive"))
      (node (ref "C110") (pin "2") (pinfunction "2_2") (pintype "passive"))
      (node (ref "C111") (pin "2") (pinfunction "2_2") (pintype "passive"))
      (node (ref "C112") (pin "2") (pinfunction "2_2") (pintype "passive"))
      (node (ref "C113") (pin "2") (pinfunction "2_2") (pintype "passive"))
      (node (ref "C121") (pin "2") (pinfunction "2_2") (pintype "passive"))
      (node (ref "C122") (pin "1") (pinfunction "1_1") (pintype "passive"))
      (node (ref "C123") (pin "1") (pinfunction "1_1") (pintype "passive"))
      (node (ref "C14") (pin "2") (pinfunction "2_2") (pintype "passive"))
      (node (ref "C15") (pin "2") (pinfunction "2_2") (pintype "passive"))
      (node (ref "C16") (pin "2") (pinfunction "2_2") (pintype "passive"))
      (node (ref "C17") (pin "2") (pinfunction "2_2") (pintype "passive"))
      (node (ref "C18") (pin "1") (pinfunction "1_1") (pintype "passive"))
      (node (ref "C19") (pin "1") (pinfunction "1_1") (pintype "passive"))
      (node (ref "C20") (pin "2") (pinfunction "2_2") (pintype "passive"))
      (node (ref "C21") (pin "2") (pinfunction "2_2") (pintype "passive"))
      (node (ref "C23") (pin "2") (pinfunction "2_2") (pintype "passive"))
      (node (ref "C24") (pin "2") (pinfunction "2_2") (pintype "passive"))
      (node (ref "C25") (pin "1") (pinfunction "1_1") (pintype "passive"))
      (node (ref "C26") (pin "1") (pinfunction "1_1") (pintype "passive"))
      (node (ref "C27") (pin "-") (pinfunction "-_-") (pintype "passive"))
      (node (ref "C28") (pin "1") (pinfunction "1_1") (pintype "passive"))
      (node (ref "C29") (pin "2") (pinfunction "2_2") (pintype "passive"))
      (node (ref "C30") (pin "-") (pinfunction "-_-") (pintype "passive"))
      (node (ref "C31") (pin "1") (pinfunction "1_1") (pintype "passive"))
      (node (ref "C401") (pin "1") (pinfunction "1_1") (pintype "passive"))
      (node (ref "C402") (pin "2") (pinfunction "2_2") (pintype "passive"))
      (node (ref "C403") (pin "-") (pinfunction "-_-") (pintype "passive"))
      (node (ref "C404") (pin "1") (pinfunction "1_1") (pintype "passive"))
      (node (ref "C405") (pin "2") (pinfunction "2_2") (pintype "passive"))
      (node (ref "C406") (pin "2") (pinfunction "2_2") (pintype "passive"))
      (node (ref "C407") (pin "2") (pinfunction "2_2") (pintype "passive"))
      (node (ref "C408") (pin "2") (pinfunction "2_2") (pintype "passive"))
      (node (ref "C409") (pin "2") (pinfunction "2_2") (pintype "passive"))
      (node (ref "C410") (pin "2") (pinfunction "2_2") (pintype "passive"))
      (node (ref "C411") (pin "2") (pinfunction "2_2") (pintype "passive"))
      (node (ref "C412") (pin "2") (pinfunction "2_2") (pintype "passive"))
      (node (ref "IC401") (pin "27") (pinfunction "TSTPLL/48MCLK_27") (pintype "bidirectional"))
      (node (ref "IC401") (pin "28") (pinfunction "GND_28") (pintype "power_in"))
      (node (ref "IC401") (pin "31") (pinfunction "TSTMODE_31") (pintype "input"))
      (node (ref "IC401") (pin "7") (pinfunction "GND_7") (pintype "power_in"))
      (node (ref "J1") (pin "4") (pinfunction "4_4") (pintype "passive"))
      (node (ref "J10") (pin "1") (pinfunction "1_1") (pintype "passive"))
      (node (ref "J10") (pin "2") (pinfunction "2_2") (pintype "passive"))
      (node (ref "J3") (pin "1") (pinfunction "1_1") (pintype "passive"))
      (node (ref "J3") (pin "2") (pinfunction "2_2") (pintype "passive"))
      (node (ref "J401") (pin "GND") (pinfunction "GND_GND") (pintype "input"))
      (node (ref "J5") (pin "2") (pinfunction "2_2") (pintype "passive"))
      (node (ref "JP3") (pin "1") (pinfunction "1_1") (pintype "passive"))
      (node (ref "JP3") (pin "2") (pinfunction "2_2") (pintype "passive"))
      (node (ref "LED1") (pin "C") (pinfunction "C_C") (pintype "passive"))
      (node (ref "LED101") (pin "C") (pinfunction "C_C") (pintype "passive"))
      (node (ref "LED102") (pin "C") (pinfunction "C_C") (pintype "passive"))
      (node (ref "LED2") (pin "C") (pinfunction "C_C") (pintype "passive"))
      (node (ref "MSP101") (pin "14") (pinfunction "14_14") (pintype "power_in"))
      (node (ref "MSP101") (pin "16") (pinfunction "16_16") (pintype "power_in"))
      (node (ref "MSP101") (pin "39") (pinfunction "39_39") (pintype "power_in"))
      (node (ref "MSP101") (pin "49") (pinfunction "49_49") (pintype "power_in"))
      (node (ref "MSP101") (pin "56") (pinfunction "56_56") (pintype "power_in"))
      (node (ref "MSP101") (pin "TP") (pinfunction "TP_TP") (pintype "power_in"))
      (node (ref "Q101") (pin "2") (pinfunction "2_2") (pintype "passive"))
      (node (ref "Q2") (pin "P3") (pinfunction "GND_P3") (pintype "power_in"))
      (node (ref "Q4") (pin "2") (pinfunction "2_2") (pintype "passive"))
      (node (ref "Q401") (pin "2") (pinfunction "2_2") (pintype "passive"))
      (node (ref "R106") (pin "1") (pinfunction "1_1") (pintype "passive"))
      (node (ref "R122") (pin "2") (pinfunction "2_2") (pintype "passive"))
      (node (ref "R125") (pin "2") (pinfunction "2_2") (pintype "passive"))
      (node (ref "R16") (pin "1") (pinfunction "1_1") (pintype "passive"))
      (node (ref "R401") (pin "2") (pinfunction "2_2") (pintype "passive"))
      (node (ref "R408") (pin "1") (pinfunction "1_1") (pintype "passive"))
      (node (ref "R409") (pin "1") (pinfunction "1_1") (pintype "passive"))
      (node (ref "R412") (pin "1") (pinfunction "1_1") (pintype "passive"))
      (node (ref "R413") (pin "1") (pinfunction "1_1") (pintype "passive"))
      (node (ref "R414") (pin "2") (pinfunction "2_2") (pintype "passive"))
      (node (ref "R415") (pin "2") (pinfunction "2_2") (pintype "passive"))
      (node (ref "R418") (pin "2") (pinfunction "2_2") (pintype "passive"))
      (node (ref "R419") (pin "2") (pinfunction "2_2") (pintype "passive"))
      (node (ref "S1") (pin "2") (pinfunction "S_2") (pintype "passive"))
      (node (ref "S2") (pin "2") (pinfunction "S_2") (pintype "passive"))
      (node (ref "S3") (pin "1") (pinfunction "P_1") (pintype "passive"))
      (node (ref "TP104") (pin "1") (pinfunction "1_1") (pintype "passive"))
      (node (ref "U402") (pin "1") (pinfunction "MODE_1") (pintype "input"))
      (node (ref "U402") (pin "4") (pinfunction "GND_4") (pintype "power_in"))
      (node (ref "U404") (pin "4") (pinfunction "GND_4") (pintype "power_in"))
      (node (ref "U6") (pin "14") (pinfunction "14_14") (pintype "power_in"))
      (node (ref "U6") (pin "19") (pinfunction "19_19") (pintype "power_in"))
      (node (ref "U6") (pin "49") (pinfunction "49_49") (pintype "power_in"))
      (node (ref "U6") (pin "61") (pinfunction "61_61") (pintype "power_in"))
      (node (ref "U6") (pin "68") (pinfunction "68_68") (pintype "power_in"))
    )
    (net (code "31") (name "HUB_DM1") (class "Default")
      (node (ref "R31") (pin "1") (pinfunction "1_1") (pintype "passive"))
      (node (ref "R416") (pin "2") (pinfunction "2_2") (pintype "passive"))
      (node (ref "R419") (pin "1") (pinfunction "1_1") (pintype "passive"))
    )
    (net (code "32") (name "HUB_DM2") (class "Default")
      (node (ref "R103") (pin "1") (pinfunction "1_1") (pintype "passive"))
      (node (ref "R410") (pin "2") (pinfunction "2_2") (pintype "passive"))
      (node (ref "R415") (pin "1") (pinfunction "1_1") (pintype "passive"))
    )
    (net (code "33") (name "HUB_DP1") (class "Default")
      (node (ref "R32") (pin "1") (pinfunction "1_1") (pintype "passive"))
      (node (ref "R417") (pin "2") (pinfunction "2_2") (pintype "passive"))
      (node (ref "R418") (pin "1") (pinfunction "1_1") (pintype "passive"))
    )
    (net (code "34") (name "HUB_DP2") (class "Default")
      (node (ref "R104") (pin "1") (pinfunction "1_1") (pintype "passive"))
      (node (ref "R411") (pin "2") (pinfunction "2_2") (pintype "passive"))
      (node (ref "R414") (pin "1") (pinfunction "1_1") (pintype "passive"))
    )
    (net (code "35") (name "Net-(C15-Pad1)") (class "Default")
      (node (ref "C15") (pin "1") (pinfunction "1_1") (pintype "passive"))
      (node (ref "U6") (pin "67") (pinfunction "67_67") (pintype "power_in"))
    )
    (net (code "36") (name "Net-(C16-Pad1)") (class "Default")
      (node (ref "C16") (pin "1") (pinfunction "1_1") (pintype "passive"))
      (node (ref "U6") (pin "66") (pinfunction "66_66") (pintype "power_in"))
    )
    (net (code "37") (name "Net-(C18-Pad2)") (class "Default")
      (node (ref "C18") (pin "2") (pinfunction "2_2") (pintype "passive"))
      (node (ref "U6") (pin "20") (pinfunction "20_20") (pintype "power_in"))
    )
    (net (code "38") (name "Net-(C29-Pad1)") (class "Default")
      (node (ref "C29") (pin "1") (pinfunction "1_1") (pintype "passive"))
      (node (ref "R28") (pin "1") (pinfunction "1_1") (pintype "passive"))
      (node (ref "U6") (pin "11") (pinfunction "11_11") (pintype "power_in"))
    )
    (net (code "39") (name "Net-(C101-Pad1)") (class "Default")
      (node (ref "C101") (pin "1") (pinfunction "1_1") (pintype "passive"))
      (node (ref "MSP101") (pin "17") (pinfunction "17_17") (pintype "power_in"))
    )
    (net (code "40") (name "Net-(IC401B-DM0)") (class "Default")
      (node (ref "C406") (pin "1") (pinfunction "1_1") (pintype "passive"))
      (node (ref "IC401") (pin "2") (pinfunction "DM0_2") (pintype "bidirectional"))
      (node (ref "R406") (pin "1") (pinfunction "1_1") (pintype "passive"))
    )
    (net (code "41") (name "Net-(IC401B-DM1)") (class "Default")
      (node (ref "C412") (pin "1") (pinfunction "1_1") (pintype "passive"))
      (node (ref "IC401") (pin "11") (pinfunction "DM1_11") (pintype "bidirectional"))
      (node (ref "R416") (pin "1") (pinfunction "1_1") (pintype "passive"))
    )
    (net (code "42") (name "Net-(IC401B-DM2)") (class "Default")
      (node (ref "C410") (pin "1") (pinfunction "1_1") (pintype "passive"))
      (node (ref "IC401") (pin "15") (pinfunction "DM2_15") (pintype "bidirectional"))
      (node (ref "R410") (pin "1") (pinfunction "1_1") (pintype "passive"))
    )
    (net (code "43") (name "Net-(IC401B-DM3)") (class "Default")
      (node (ref "IC401") (pin "19") (pinfunction "DM3_19") (pintype "bidirectional"))
      (node (ref "R413") (pin "2") (pinfunction "2_2") (pintype "passive"))
    )
    (net (code "44") (name "Net-(IC401B-DM4)") (class "Default")
      (node (ref "IC401") (pin "23") (pinfunction "DM4_23") (pintype "bidirectional"))
      (node (ref "R409") (pin "2") (pinfunction "2_2") (pintype "passive"))
    )
    (net (code "45") (name "Net-(IC401B-DP0)") (class "Default")
      (node (ref "C405") (pin "1") (pinfunction "1_1") (pintype "passive"))
      (node (ref "IC401") (pin "1") (pinfunction "DP0_1") (pintype "bidirectional"))
      (node (ref "R403") (pin "2") (pinfunction "2_2") (pintype "passive"))
      (node (ref "R405") (pin "1") (pinfunction "1_1") (pintype "passive"))
    )
    (net (code "46") (name "Net-(IC401B-DP1)") (class "Default")
      (node (ref "C411") (pin "1") (pinfunction "1_1") (pintype "passive"))
      (node (ref "IC401") (pin "12") (pinfunction "DP1_12") (pintype "bidirectional"))
      (node (ref "R417") (pin "1") (pinfunction "1_1") (pintype "passive"))
    )
    (net (code "47") (name "Net-(IC401B-DP2)") (class "Default")
      (node (ref "C409") (pin "1") (pinfunction "1_1") (pintype "passive"))
      (node (ref "IC401") (pin "16") (pinfunction "DP2_16") (pintype "bidirectional"))
      (node (ref "R411") (pin "1") (pinfunction "1_1") (pintype "passive"))
    )
    (net (code "48") (name "Net-(IC401B-DP3)") (class "Default")
      (node (ref "IC401") (pin "20") (pinfunction "DP3_20") (pintype "bidirectional"))
      (node (ref "R412") (pin "2") (pinfunction "2_2") (pintype "passive"))
    )
    (net (code "49") (name "Net-(IC401B-DP4)") (class "Default")
      (node (ref "IC401") (pin "24") (pinfunction "DP4_24") (pintype "bidirectional"))
      (node (ref "R408") (pin "2") (pinfunction "2_2") (pintype "passive"))
    )
    (net (code "50") (name "Net-(IC401B-XTAL1)") (class "Default")
      (node (ref "IC401") (pin "30") (pinfunction "XTAL1_30") (pintype "input"))
      (node (ref "Q401") (pin "1") (pinfunction "1_1") (pintype "passive"))
    )
    (net (code "51") (name "Net-(IC401B-XTAL2)") (class "Default")
      (node (ref "IC401") (pin "29") (pinfunction "XTAL2_29") (pintype "output"))
      (node (ref "R407") (pin "2") (pinfunction "2_2") (pintype "passive"))
    )
    (net (code "52") (name "Net-(IC401B-~{RESET})") (class "Default")
      (node (ref "C408") (pin "1") (pinfunction "1_1") (pintype "passive"))
      (node (ref "IC401") (pin "4") (pinfunction "~{RESET}_4") (pintype "input"))
      (node (ref "R404") (pin "2") (pinfunction "2_2") (pintype "passive"))
    )
    (net (code "53") (name "Net-(J401-PadSHIELD1)") (class "Default")
      (node (ref "J401") (pin "SHIELD1") (pinfunction "SHIELD1_SHIELD1") (pintype "bidirectional"))
      (node (ref "R401") (pin "1") (pinfunction "1_1") (pintype "passive"))
    )
    (net (code "54") (name "Net-(JP8-Pad2)") (class "Default")
      (node (ref "JP8") (pin "2") (pinfunction "2_2") (pintype "passive"))
      (node (ref "R29") (pin "1") (pinfunction "1_1") (pintype "passive"))
    )
    (net (code "55") (name "Net-(L401-1)") (class "Default")
      (node (ref "L401") (pin "P$1") (pinfunction "1_P$1") (pintype "passive"))
      (node (ref "U402") (pin "2") (pinfunction "SW_2") (pintype "output"))
    )
    (net (code "56") (name "Net-(LED1-PadA)") (class "Default")
      (node (ref "LED1") (pin "A") (pinfunction "A_A") (pintype "passive"))
      (node (ref "R29") (pin "2") (pinfunction "2_2") (pintype "passive"))
    )
    (net (code "57") (name "Net-(LED2-PadA)") (class "Default")
      (node (ref "LED2") (pin "A") (pinfunction "A_A") (pintype "passive"))
      (node (ref "R30") (pin "2") (pinfunction "2_2") (pintype "passive"))
    )
    (net (code "58") (name "Net-(LED101-PadA)") (class "Default")
      (node (ref "LED101") (pin "A") (pinfunction "A_A") (pintype "passive"))
      (node (ref "R101") (pin "1") (pinfunction "1_1") (pintype "passive"))
    )
    (net (code "59") (name "Net-(LED102-PadA)") (class "Default")
      (node (ref "LED102") (pin "A") (pinfunction "A_A") (pintype "passive"))
      (node (ref "R102") (pin "1") (pinfunction "1_1") (pintype "passive"))
    )
    (net (code "60") (name "Net-(Q2-1)") (class "Default")
      (node (ref "C25") (pin "2") (pinfunction "2_2") (pintype "passive"))
      (node (ref "Q2") (pin "P1") (pinfunction "1_P1") (pintype "bidirectional"))
      (node (ref "U6") (pin "13") (pinfunction "13_13") (pintype "bidirectional"))
    )
    (net (code "61") (name "Net-(Q2-2)") (class "Default")
      (node (ref "C26") (pin "2") (pinfunction "2_2") (pintype "passive"))
      (node (ref "Q2") (pin "P2") (pinfunction "2_P2") (pintype "bidirectional"))
      (node (ref "U6") (pin "12") (pinfunction "12_12") (pintype "bidirectional"))
    )
    (net (code "62") (name "Net-(Q4-Pad1)") (class "Default")
      (node (ref "Q4") (pin "1") (pinfunction "1_1") (pintype "passive"))
      (node (ref "U6") (pin "70") (pinfunction "70_70") (pintype "bidirectional"))
    )
    (net (code "63") (name "Net-(Q4-Pad3)") (class "Default")
      (node (ref "Q4") (pin "3") (pinfunction "3_3") (pintype "passive"))
      (node (ref "U6") (pin "69") (pinfunction "69_69") (pintype "bidirectional"))
    )
    (net (code "64") (name "Net-(Q401-Pad3)") (class "Default")
      (node (ref "Q401") (pin "3") (pinfunction "3_3") (pintype "passive"))
      (node (ref "R407") (pin "1") (pinfunction "1_1") (pintype "passive"))
    )
    (net (code "65") (name "Net-(S5-S)") (class "Default")
      (node (ref "R14") (pin "1") (pinfunction "1_1") (pintype "passive"))
      (node (ref "S5") (pin "2") (pinfunction "S_2") (pintype "passive"))
    )
    (net (code "66") (name "Net-(U404-IO1)") (class "Default")
      (node (ref "J401") (pin "D-") (pinfunction "D-_D-") (pintype "input"))
      (node (ref "R406") (pin "2") (pinfunction "2_2") (pintype "passive"))
      (node (ref "U404") (pin "3") (pinfunction "IO1_3") (pintype "bidirectional"))
    )
    (net (code "67") (name "Net-(U404-IO2)") (class "Default")
      (node (ref "J401") (pin "D+") (pinfunction "D+_D+") (pintype "input"))
      (node (ref "R405") (pin "2") (pinfunction "2_2") (pintype "passive"))
      (node (ref "U404") (pin "5") (pinfunction "IO2_5") (pintype "bidirectional"))
    )
    (net (code "68") (name "P1.0") (class "Default")
      (node (ref "JP8") (pin "1") (pinfunction "1_1") (pintype "passive"))
      (node (ref "U6") (pin "21") (pinfunction "21_21") (pintype "bidirectional"))
    )
    (net (code "69") (name "P1.1") (class "Default")
      (node (ref "S2") (pin "1") (pinfunction "P_1") (pintype "passive"))
      (node (ref "U6") (pin "22") (pinfunction "22_22") (pintype "bidirectional"))
    )
    (net (code "70") (name "P1.2") (class "Default")
      (node (ref "J5") (pin "11") (pinfunction "11_11") (pintype "passive"))
      (node (ref "U6") (pin "23") (pinfunction "23_23") (pintype "bidirectional"))
    )
    (net (code "71") (name "P1.3") (class "Default")
      (node (ref "J5") (pin "9") (pinfunction "9_9") (pintype "passive"))
      (node (ref "U6") (pin "24") (pinfunction "24_24") (pintype "bidirectional"))
    )
    (net (code "72") (name "P1.4") (class "Default")
      (node (ref "J5") (pin "7") (pinfunction "7_7") (pintype "passive"))
      (node (ref "U6") (pin "25") (pinfunction "25_25") (pintype "bidirectional"))
    )
    (net (code "73") (name "P1.5") (class "Default")
      (node (ref "J5") (pin "5") (pinfunction "5_5") (pintype "passive"))
      (node (ref "U6") (pin "26") (pinfunction "26_26") (pintype "bidirectional"))
    )
    (net (code "74") (name "P1.6") (class "Default")
      (node (ref "J1") (pin "9") (pinfunction "9_9") (pintype "passive"))
      (node (ref "U6") (pin "27") (pinfunction "27_27") (pintype "bidirectional"))
    )
    (net (code "75") (name "P1.7") (class "Default")
      (node (ref "JP6.3") (pin "2") (pinfunction "2_2") (pintype "passive"))
      (node (ref "U6") (pin "28") (pinfunction "28_28") (pintype "bidirectional"))
    )
    (net (code "76") (name "P2.0") (class "Default")
      (node (ref "J5") (pin "4") (pinfunction "4_4") (pintype "passive"))
      (node (ref "U6") (pin "29") (pinfunction "29_29") (pintype "bidirectional"))
    )
    (net (code "77") (name "P2.1") (class "Default")
      (node (ref "S1") (pin "1") (pinfunction "P_1") (pintype "passive"))
      (node (ref "U6") (pin "30") (pinfunction "30_30") (pintype "bidirectional"))
    )
    (net (code "78") (name "P2.2") (class "Default")
      (node (ref "J5") (pin "6") (pinfunction "6_6") (pintype "passive"))
      (node (ref "U6") (pin "31") (pinfunction "31_31") (pintype "bidirectional"))
    )
    (net (code "79") (name "P2.3") (class "Default")
      (node (ref "J5") (pin "18") (pinfunction "18_18") (pintype "passive"))
      (node (ref "U6") (pin "32") (pinfunction "32_32") (pintype "bidirectional"))
    )
    (net (code "80") (name "P2.4") (class "Default")
      (node (ref "J5") (pin "3") (pinfunction "3_3") (pintype "passive"))
      (node (ref "U6") (pin "33") (pinfunction "33_33") (pintype "bidirectional"))
    )
    (net (code "81") (name "P2.5") (class "Default")
      (node (ref "J5") (pin "1") (pinfunction "1_1") (pintype "passive"))
      (node (ref "U6") (pin "34") (pinfunction "34_34") (pintype "bidirectional"))
    )
    (net (code "82") (name "P2.6") (class "Default")
      (node (ref "J5") (pin "16") (pinfunction "16_16") (pintype "passive"))
      (node (ref "U6") (pin "35") (pinfunction "35_35") (pintype "bidirectional"))
    )
    (net (code "83") (name "P2.7") (class "Default")
      (node (ref "J1") (pin "15") (pinfunction "15_15") (pintype "passive"))
      (node (ref "U6") (pin "36") (pinfunction "36_36") (pintype "bidirectional"))
    )
    (net (code "84") (name "P3.0") (class "Default")
      (node (ref "J5") (pin "12") (pinfunction "12_12") (pintype "passive"))
      (node (ref "U6") (pin "37") (pinfunction "37_37") (pintype "bidirectional"))
    )
    (net (code "85") (name "P3.1") (class "Default")
      (node (ref "J5") (pin "14") (pinfunction "14_14") (pintype "passive"))
      (node (ref "U6") (pin "38") (pinfunction "38_38") (pintype "bidirectional"))
    )
    (net (code "86") (name "P3.2") (class "Default")
      (node (ref "J1") (pin "13") (pinfunction "13_13") (pintype "passive"))
      (node (ref "U6") (pin "39") (pinfunction "39_39") (pintype "bidirectional"))
    )
    (net (code "87") (name "P3.3") (class "Default")
      (node (ref "J1") (pin "7") (pinfunction "7_7") (pintype "passive"))
      (node (ref "U6") (pin "40") (pinfunction "40_40") (pintype "bidirectional"))
    )
    (net (code "88") (name "P3.4") (class "Default")
      (node (ref "J1") (pin "5") (pinfunction "5_5") (pintype "passive"))
      (node (ref "U6") (pin "41") (pinfunction "41_41") (pintype "bidirectional"))
    )
    (net (code "89") (name "P3.5") (class "Default")
      (node (ref "J1") (pin "20") (pinfunction "20_20") (pintype "passive"))
      (node (ref "U6") (pin "42") (pinfunction "42_42") (pintype "bidirectional"))
    )
    (net (code "90") (name "P3.6") (class "Default")
      (node (ref "J1") (pin "18") (pinfunction "18_18") (pintype "passive"))
      (node (ref "U6") (pin "43") (pinfunction "43_43") (pintype "bidirectional"))
    )
    (net (code "91") (name "P3.7") (class "Default")
      (node (ref "J5") (pin "17") (pinfunction "17_17") (pintype "passive"))
      (node (ref "U6") (pin "44") (pinfunction "44_44") (pintype "bidirectional"))
    )
    (net (code "92") (name "P4.0") (class "Default")
      (node (ref "J5") (pin "15") (pinfunction "15_15") (pintype "passive"))
      (node (ref "U6") (pin "45") (pinfunction "45_45") (pintype "bidirectional"))
    )
    (net (code "93") (name "P4.1") (class "Default")
      (node (ref "J1") (pin "19") (pinfunction "19_19") (pintype "passive"))
      (node (ref "U6") (pin "46") (pinfunction "46_46") (pintype "bidirectional"))
    )
    (net (code "94") (name "P4.2") (class "Default")
      (node (ref "J1") (pin "17") (pinfunction "17_17") (pintype "passive"))
      (node (ref "U6") (pin "47") (pinfunction "47_47") (pintype "bidirectional"))
    )
    (net (code "95") (name "P4.3") (class "Default")
      (node (ref "J5") (pin "13") (pinfunction "13_13") (pintype "passive"))
      (node (ref "U6") (pin "48") (pinfunction "48_48") (pintype "bidirectional"))
    )
    (net (code "96") (name "P4.4{slash}UCA1TXD") (class "Default")
      (node (ref "JP6.1") (pin "2") (pinfunction "2_2") (pintype "passive"))
      (node (ref "U6") (pin "51") (pinfunction "51_51") (pintype "bidirectional"))
    )
    (net (code "97") (name "P4.5{slash}UCA1RXD") (class "Default")
      (node (ref "JP6.2") (pin "2") (pinfunction "2_2") (pintype "passive"))
      (node (ref "U6") (pin "52") (pinfunction "52_52") (pintype "bidirectional"))
    )
    (net (code "98") (name "P4.7") (class "Default")
      (node (ref "R30") (pin "1") (pinfunction "1_1") (pintype "passive"))
      (node (ref "U6") (pin "54") (pinfunction "54_54") (pintype "bidirectional"))
    )
    (net (code "99") (name "P6.0") (class "Default")
      (node (ref "J1") (pin "6") (pinfunction "6_6") (pintype "passive"))
      (node (ref "U6") (pin "77") (pinfunction "77_77") (pintype "bidirectional"))
    )
    (net (code "100") (name "P6.1") (class "Default")
      (node (ref "J1") (pin "8") (pinfunction "8_8") (pintype "passive"))
      (node (ref "U6") (pin "78") (pinfunction "78_78") (pintype "bidirectional"))
    )
    (net (code "101") (name "P6.2") (class "Default")
      (node (ref "J1") (pin "10") (pinfunction "10_10") (pintype "passive"))
      (node (ref "U6") (pin "79") (pinfunction "79_79") (pintype "bidirectional"))
    )
    (net (code "102") (name "P6.3") (class "Default")
      (node (ref "J1") (pin "12") (pinfunction "12_12") (pintype "passive"))
      (node (ref "U6") (pin "80") (pinfunction "80_80") (pintype "bidirectional"))
    )
    (net (code "103") (name "P6.4") (class "Default")
      (node (ref "J1") (pin "14") (pinfunction "14_14") (pintype "passive"))
      (node (ref "U6") (pin "1") (pinfunction "1_1") (pintype "bidirectional"))
    )
    (net (code "104") (name "P6.5") (class "Default")
      (node (ref "J1") (pin "3") (pinfunction "3_3") (pintype "passive"))
      (node (ref "U6") (pin "2") (pinfunction "2_2") (pintype "bidirectional"))
    )
    (net (code "105") (name "P6.6") (class "Default")
      (node (ref "J1") (pin "11") (pinfunction "11_11") (pintype "passive"))
      (node (ref "U6") (pin "3") (pinfunction "3_3") (pintype "bidirectional"))
    )
    (net (code "106") (name "P6.7") (class "Default")
      (node (ref "JP6.4") (pin "2") (pinfunction "2_2") (pintype "passive"))
      (node (ref "U6") (pin "4") (pinfunction "4_4") (pintype "bidirectional"))
    )
    (net (code "107") (name "P7.0") (class "Default")
      (node (ref "J1") (pin "16") (pinfunction "16_16") (pintype "passive"))
      (node (ref "U6") (pin "5") (pinfunction "5_5") (pintype "bidirectional"))
    )
    (net (code "108") (name "P7.4") (class "Default")
      (node (ref "J5") (pin "8") (pinfunction "8_8") (pintype "passive"))
      (node (ref "U6") (pin "57") (pinfunction "57_57") (pintype "bidirectional"))
    )
    (net (code "109") (name "P8.1") (class "Default")
      (node (ref "J5") (pin "20") (pinfunction "20_20") (pintype "passive"))
      (node (ref "U6") (pin "16") (pinfunction "16_16") (pintype "bidirectional"))
    )
    (net (code "110") (name "P8.2") (class "Default")
      (node (ref "J5") (pin "19") (pinfunction "19_19") (pintype "passive"))
      (node (ref "U6") (pin "17") (pinfunction "17_17") (pintype "bidirectional"))
    )
    (net (code "111") (name "RST{slash}SBWTDIO") (class "Default")
      (node (ref "C17") (pin "1") (pinfunction "1_1") (pintype "passive"))
      (node (ref "J5") (pin "10") (pinfunction "10_10") (pintype "passive"))
      (node (ref "JP4.2") (pin "2") (pinfunction "2_2") (pintype "passive"))
      (node (ref "R27") (pin "1") (pinfunction "1_1") (pintype "passive"))
      (node (ref "S3") (pin "2") (pinfunction "S_2") (pintype "passive"))
      (node (ref "U6") (pin "76") (pinfunction "76_76") (pintype "bidirectional"))
    )
    (net (code "112") (name "TARGET_DM") (class "Default")
      (node (ref "C24") (pin "1") (pinfunction "1_1") (pintype "passive"))
      (node (ref "R31") (pin "2") (pinfunction "2_2") (pintype "passive"))
      (node (ref "U6") (pin "64") (pinfunction "64_64") (pintype "bidirectional"))
    )
    (net (code "113") (name "TARGET_DP") (class "Default")
      (node (ref "C23") (pin "1") (pinfunction "1_1") (pintype "passive"))
      (node (ref "R15") (pin "2") (pinfunction "2_2") (pintype "passive"))
      (node (ref "R32") (pin "2") (pinfunction "2_2") (pintype "passive"))
      (node (ref "U6") (pin "62") (pinfunction "62_62") (pintype "bidirectional"))
    )
    (net (code "114") (name "TARGET_PUR") (class "Default")
      (node (ref "R14") (pin "2") (pinfunction "2_2") (pintype "passive"))
      (node (ref "R15") (pin "1") (pinfunction "1_1") (pintype "passive"))
      (node (ref "R16") (pin "2") (pinfunction "2_2") (pintype "passive"))
      (node (ref "U6") (pin "63") (pinfunction "63_63") (pintype "bidirectional"))
    )
    (net (code "115") (name "TEST{slash}SBWTCK") (class "Default")
      (node (ref "JP4.1") (pin "2") (pinfunction "2_2") (pintype "passive"))
      (node (ref "U6") (pin "71") (pinfunction "71_71") (pintype "input"))
    )
    (net (code "116") (name "unconnected-(IC401B-EECLK-Pad5)") (class "Default")
      (node (ref "IC401") (pin "5") (pinfunction "EECLK_5") (pintype "output"))
    )
    (net (code "117") (name "unconnected-(IC401B-SUSPND-Pad32)") (class "Default")
      (node (ref "IC401") (pin "32") (pinfunction "SUSPND_32") (pintype "output"))
    )
    (net (code "118") (name "unconnected-(J401-PadNC)") (class "Default")
      (node (ref "J401") (pin "NC") (pinfunction "NC_NC") (pintype "input"))
    )
    (net (code "119") (name "unconnected-(J401-PadSHIELD2)") (class "Default")
      (node (ref "J401") (pin "SHIELD2") (pinfunction "SHIELD2_SHIELD2") (pintype "bidirectional"))
    )
    (net (code "120") (name "unconnected-(J401-PadSHIELD3)") (class "Default")
      (node (ref "J401") (pin "SHIELD3") (pinfunction "SHIELD3_SHIELD3") (pintype "bidirectional"))
    )
    (net (code "121") (name "unconnected-(J401-PadSHIELD4)") (class "Default")
      (node (ref "J401") (pin "SHIELD4") (pinfunction "SHIELD4_SHIELD4") (pintype "bidirectional"))
    )
    (net (code "122") (name "unconnected-(J401-PadSHIELD5)") (class "Default")
      (node (ref "J401") (pin "SHIELD5") (pinfunction "SHIELD5_SHIELD5") (pintype "bidirectional"))
    )
    (net (code "123") (name "unconnected-(J401-PadSHIELD6)") (class "Default")
      (node (ref "J401") (pin "SHIELD6") (pinfunction "SHIELD6_SHIELD6") (pintype "bidirectional"))
    )
    (net (code "124") (name "unconnected-(JP4.3-Pad2)") (class "Default")
      (node (ref "JP4.3") (pin "2") (pinfunction "2_2") (pintype "passive"))
    )
    (net (code "125") (name "unconnected-(MSP101-Pad3)") (class "Default")
      (node (ref "MSP101") (pin "3") (pinfunction "3_3") (pintype "bidirectional"))
    )
    (net (code "126") (name "unconnected-(MSP101-Pad4)") (class "Default")
      (node (ref "MSP101") (pin "4") (pinfunction "4_4") (pintype "bidirectional"))
    )
    (net (code "127") (name "unconnected-(MSP101-Pad5)") (class "Default")
      (node (ref "MSP101") (pin "5") (pinfunction "5_5") (pintype "bidirectional"))
    )
    (net (code "128") (name "unconnected-(MSP101-Pad6)") (class "Default")
      (node (ref "MSP101") (pin "6") (pinfunction "6_6") (pintype "bidirectional"))
    )
    (net (code "129") (name "unconnected-(MSP101-Pad7)") (class "Default")
      (node (ref "MSP101") (pin "7") (pinfunction "7_7") (pintype "no_connect"))
    )
    (net (code "130") (name "unconnected-(MSP101-Pad8)") (class "Default")
      (node (ref "MSP101") (pin "8") (pinfunction "8_8") (pintype "input"))
    )
    (net (code "131") (name "unconnected-(MSP101-Pad10)") (class "Default")
      (node (ref "MSP101") (pin "10") (pinfunction "10_10") (pintype "bidirectional"))
    )
    (net (code "132") (name "unconnected-(MSP101-Pad12)") (class "Default")
      (node (ref "MSP101") (pin "12") (pinfunction "12_12") (pintype "bidirectional"))
    )
    (net (code "133") (name "unconnected-(MSP101-Pad13)") (class "Default")
      (node (ref "MSP101") (pin "13") (pinfunction "13_13") (pintype "bidirectional"))
    )
    (net (code "134") (name "unconnected-(MSP101-Pad18)") (class "Default")
      (node (ref "MSP101") (pin "18") (pinfunction "18_18") (pintype "bidirectional"))
    )
    (net (code "135") (name "unconnected-(MSP101-Pad19)") (class "Default")
      (node (ref "MSP101") (pin "19") (pinfunction "19_19") (pintype "bidirectional"))
    )
    (net (code "136") (name "unconnected-(MSP101-Pad22)") (class "Default")
      (node (ref "MSP101") (pin "22") (pinfunction "22_22") (pintype "bidirectional"))
    )
    (net (code "137") (name "unconnected-(MSP101-Pad23)") (class "Default")
      (node (ref "MSP101") (pin "23") (pinfunction "23_23") (pintype "bidirectional"))
    )
    (net (code "138") (name "unconnected-(MSP101-Pad24)") (class "Default")
      (node (ref "MSP101") (pin "24") (pinfunction "24_24") (pintype "bidirectional"))
    )
    (net (code "139") (name "unconnected-(MSP101-Pad25)") (class "Default")
      (node (ref "MSP101") (pin "25") (pinfunction "25_25") (pintype "bidirectional"))
    )
    (net (code "140") (name "unconnected-(MSP101-Pad26)") (class "Default")
      (node (ref "MSP101") (pin "26") (pinfunction "26_26") (pintype "bidirectional"))
    )
    (net (code "141") (name "unconnected-(MSP101-Pad27)") (class "Default")
      (node (ref "MSP101") (pin "27") (pinfunction "27_27") (pintype "bidirectional"))
    )
    (net (code "142") (name "unconnected-(MSP101-Pad28)") (class "Default")
      (node (ref "MSP101") (pin "28") (pinfunction "28_28") (pintype "bidirectional"))
    )
    (net (code "143") (name "unconnected-(MSP101-Pad29)") (class "Default")
      (node (ref "MSP101") (pin "29") (pinfunction "29_29") (pintype "bidirectional"))
    )
    (net (code "144") (name "unconnected-(MSP101-Pad30)") (class "Default")
      (node (ref "MSP101") (pin "30") (pinfunction "30_30") (pintype "bidirectional"))
    )
    (net (code "145") (name "unconnected-(MSP101-Pad31)") (class "Default")
      (node (ref "MSP101") (pin "31") (pinfunction "31_31") (pintype "bidirectional"))
    )
    (net (code "146") (name "unconnected-(MSP101-Pad34)") (class "Default")
      (node (ref "MSP101") (pin "34") (pinfunction "34_34") (pintype "bidirectional"))
    )
    (net (code "147") (name "unconnected-(MSP101-Pad35)") (class "Default")
      (node (ref "MSP101") (pin "35") (pinfunction "35_35") (pintype "bidirectional"))
    )
    (net (code "148") (name "unconnected-(MSP101-Pad36)") (class "Default")
      (node (ref "MSP101") (pin "36") (pinfunction "36_36") (pintype "bidirectional"))
    )
    (net (code "149") (name "unconnected-(MSP101-Pad41)") (class "Default")
      (node (ref "MSP101") (pin "41") (pinfunction "41_41") (pintype "bidirectional"))
    )
    (net (code "150") (name "unconnected-(MSP101-Pad42)") (class "Default")
      (node (ref "MSP101") (pin "42") (pinfunction "42_42") (pintype "bidirectional"))
    )
    (net (code "151") (name "unconnected-(MSP101-Pad46)") (class "Default")
      (node (ref "MSP101") (pin "46") (pinfunction "46_46") (pintype "bidirectional"))
    )
    (net (code "152") (name "unconnected-(MSP101-Pad47)") (class "Default")
      (node (ref "MSP101") (pin "47") (pinfunction "47_47") (pintype "bidirectional"))
    )
    (net (code "153") (name "unconnected-(MSP101-Pad48)") (class "Default")
      (node (ref "MSP101") (pin "48") (pinfunction "48_48") (pintype "bidirectional"))
    )
    (net (code "154") (name "unconnected-(U6-Pad6)") (class "Default")
      (node (ref "U6") (pin "6") (pinfunction "6_6") (pintype "bidirectional"))
    )
    (net (code "155") (name "unconnected-(U6-Pad7)") (class "Default")
      (node (ref "U6") (pin "7") (pinfunction "7_7") (pintype "bidirectional"))
    )
    (net (code "156") (name "unconnected-(U6-Pad8)") (class "Default")
      (node (ref "U6") (pin "8") (pinfunction "8_8") (pintype "bidirectional"))
    )
    (net (code "157") (name "unconnected-(U6-Pad9)") (class "Default")
      (node (ref "U6") (pin "9") (pinfunction "9_9") (pintype "bidirectional"))
    )
    (net (code "158") (name "unconnected-(U6-Pad10)") (class "Default")
      (node (ref "U6") (pin "10") (pinfunction "10_10") (pintype "bidirectional"))
    )
    (net (code "159") (name "unconnected-(U6-Pad15)") (class "Default")
      (node (ref "U6") (pin "15") (pinfunction "15_15") (pintype "bidirectional"))
    )
    (net (code "160") (name "unconnected-(U6-Pad53)") (class "Default")
      (node (ref "U6") (pin "53") (pinfunction "53_53") (pintype "bidirectional"))
    )
    (net (code "161") (name "unconnected-(U6-Pad55)") (class "Default")
      (node (ref "U6") (pin "55") (pinfunction "55_55") (pintype "bidirectional"))
    )
    (net (code "162") (name "unconnected-(U6-Pad56)") (class "Default")
      (node (ref "U6") (pin "56") (pinfunction "56_56") (pintype "bidirectional"))
    )
    (net (code "163") (name "unconnected-(U6-Pad58)") (class "Default")
      (node (ref "U6") (pin "58") (pinfunction "58_58") (pintype "bidirectional"))
    )
    (net (code "164") (name "unconnected-(U6-Pad59)") (class "Default")
      (node (ref "U6") (pin "59") (pinfunction "59_59") (pintype "bidirectional"))
    )
    (net (code "165") (name "unconnected-(U6-Pad60)") (class "Default")
      (node (ref "U6") (pin "60") (pinfunction "60_60") (pintype "bidirectional"))
    )
    (net (code "166") (name "unconnected-(U6-Pad72)") (class "Default")
      (node (ref "U6") (pin "72") (pinfunction "72_72") (pintype "bidirectional"))
    )
    (net (code "167") (name "unconnected-(U6-Pad73)") (class "Default")
      (node (ref "U6") (pin "73") (pinfunction "73_73") (pintype "bidirectional"))
    )
    (net (code "168") (name "unconnected-(U6-Pad74)") (class "Default")
      (node (ref "U6") (pin "74") (pinfunction "74_74") (pintype "bidirectional"))
    )
    (net (code "169") (name "unconnected-(U6-Pad75)") (class "Default")
      (node (ref "U6") (pin "75") (pinfunction "75_75") (pintype "bidirectional"))
    )
    (net (code "170") (name "unconnected-(U404-NC-Pad2)") (class "Default")
      (node (ref "U404") (pin "2") (pinfunction "NC_2") (pintype "no_connect"))
    )
    (net (code "171") (name "~{OC}") (class "Default")
      (node (ref "IC401") (pin "10") (pinfunction "~{OVRCUR1}_10") (pintype "input"))
      (node (ref "IC401") (pin "14") (pinfunction "~{OVRCUR2}_14") (pintype "input"))
      (node (ref "IC401") (pin "18") (pinfunction "~{OVRCUR3}_18") (pintype "input"))
      (node (ref "IC401") (pin "22") (pinfunction "~{OVRCUR4}_22") (pintype "input"))
      (node (ref "R402") (pin "2") (pinfunction "2_2") (pintype "passive"))
    )
    (net (code "172") (name "~{PWRON}") (class "Default")
      (node (ref "IC401") (pin "13") (pinfunction "~{PWRON2}_13") (pintype "output"))
      (node (ref "IC401") (pin "17") (pinfunction "~{PWRON3}_17") (pintype "output"))
      (node (ref "IC401") (pin "21") (pinfunction "~{PWRON4}_21") (pintype "output"))
      (node (ref "IC401") (pin "9") (pinfunction "~{PWRON1}_9") (pintype "output"))
    )
  )
)
